# NOMIDI_Controller_001.net
KiCad netlist of a schematic drawn in EAGLE
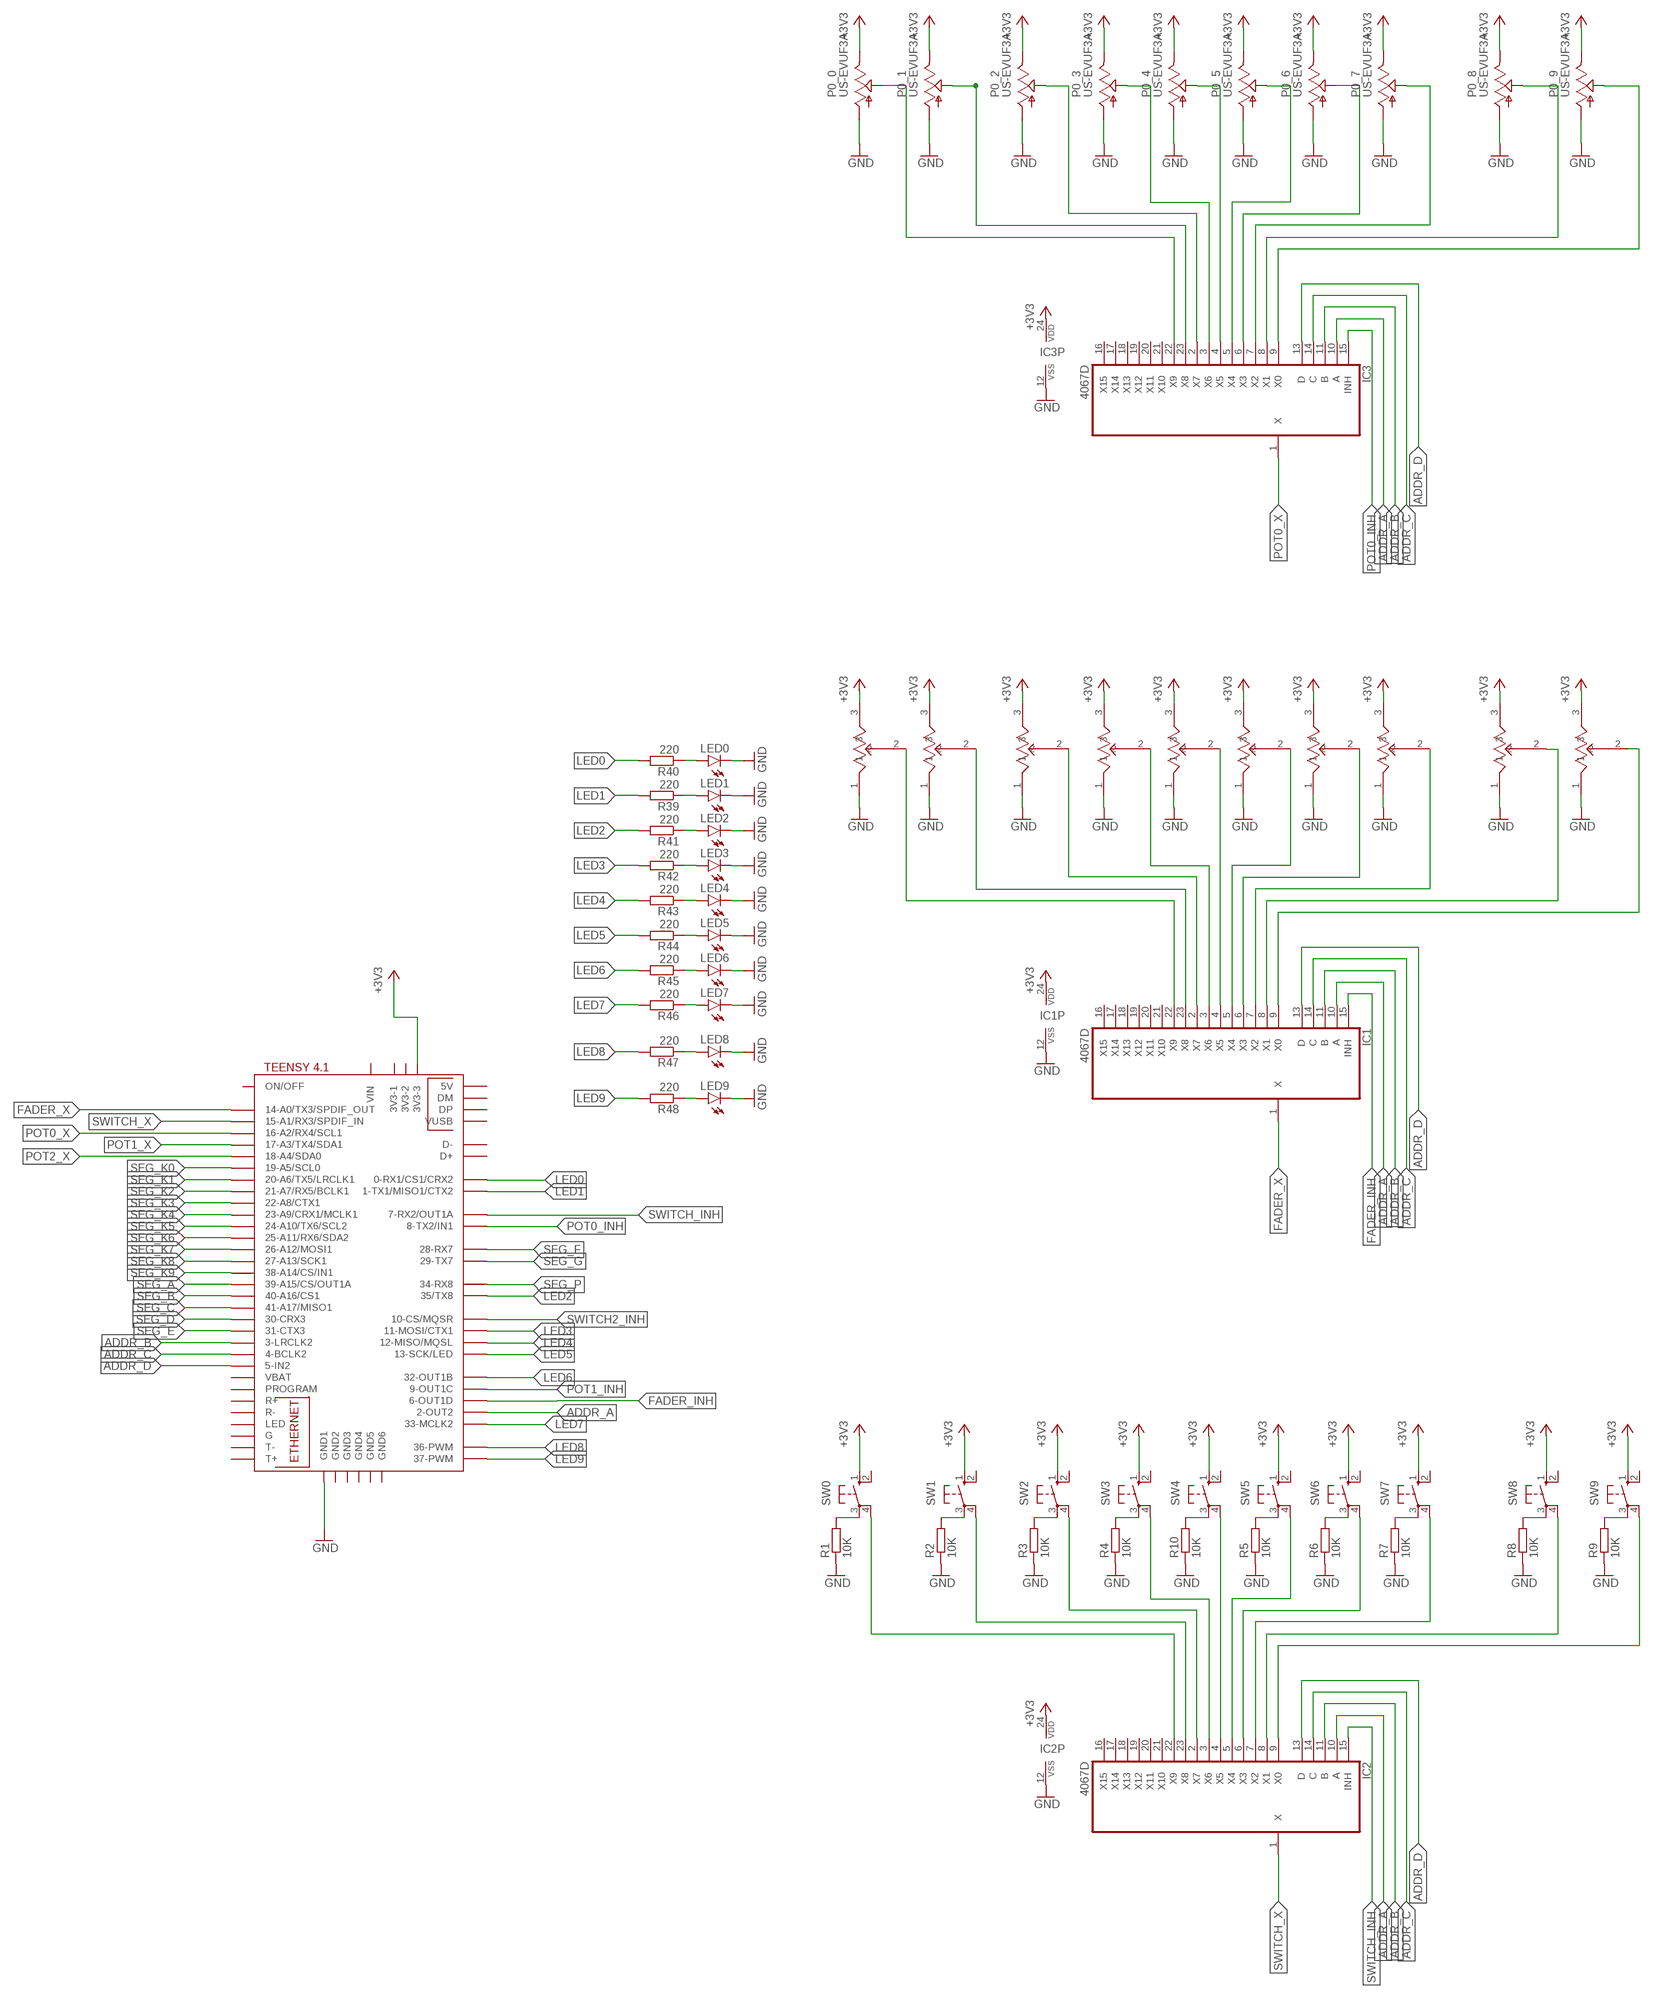
[diagram p0: schematic, sheet 1, part 1 of 3]
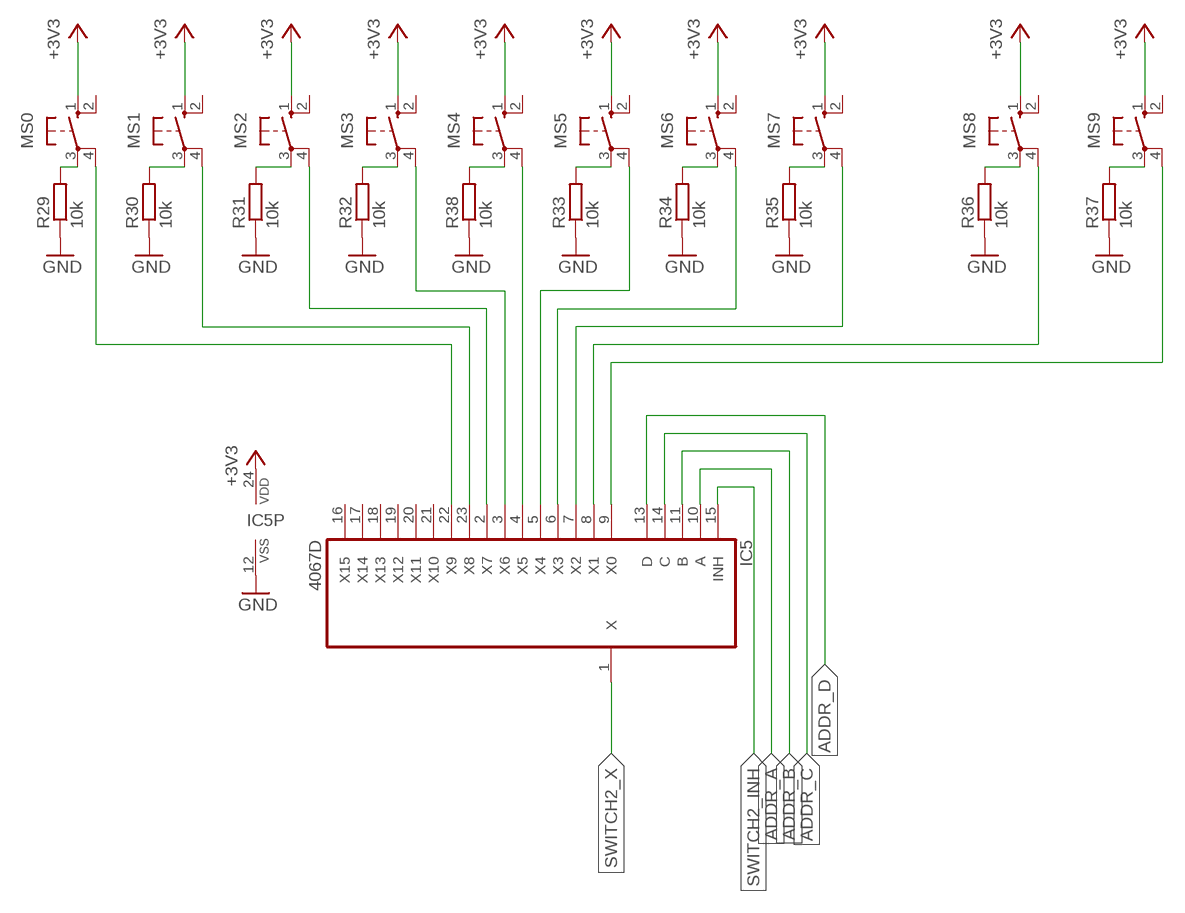
[diagram p1: schematic, sheet 1, part 2 of 3]
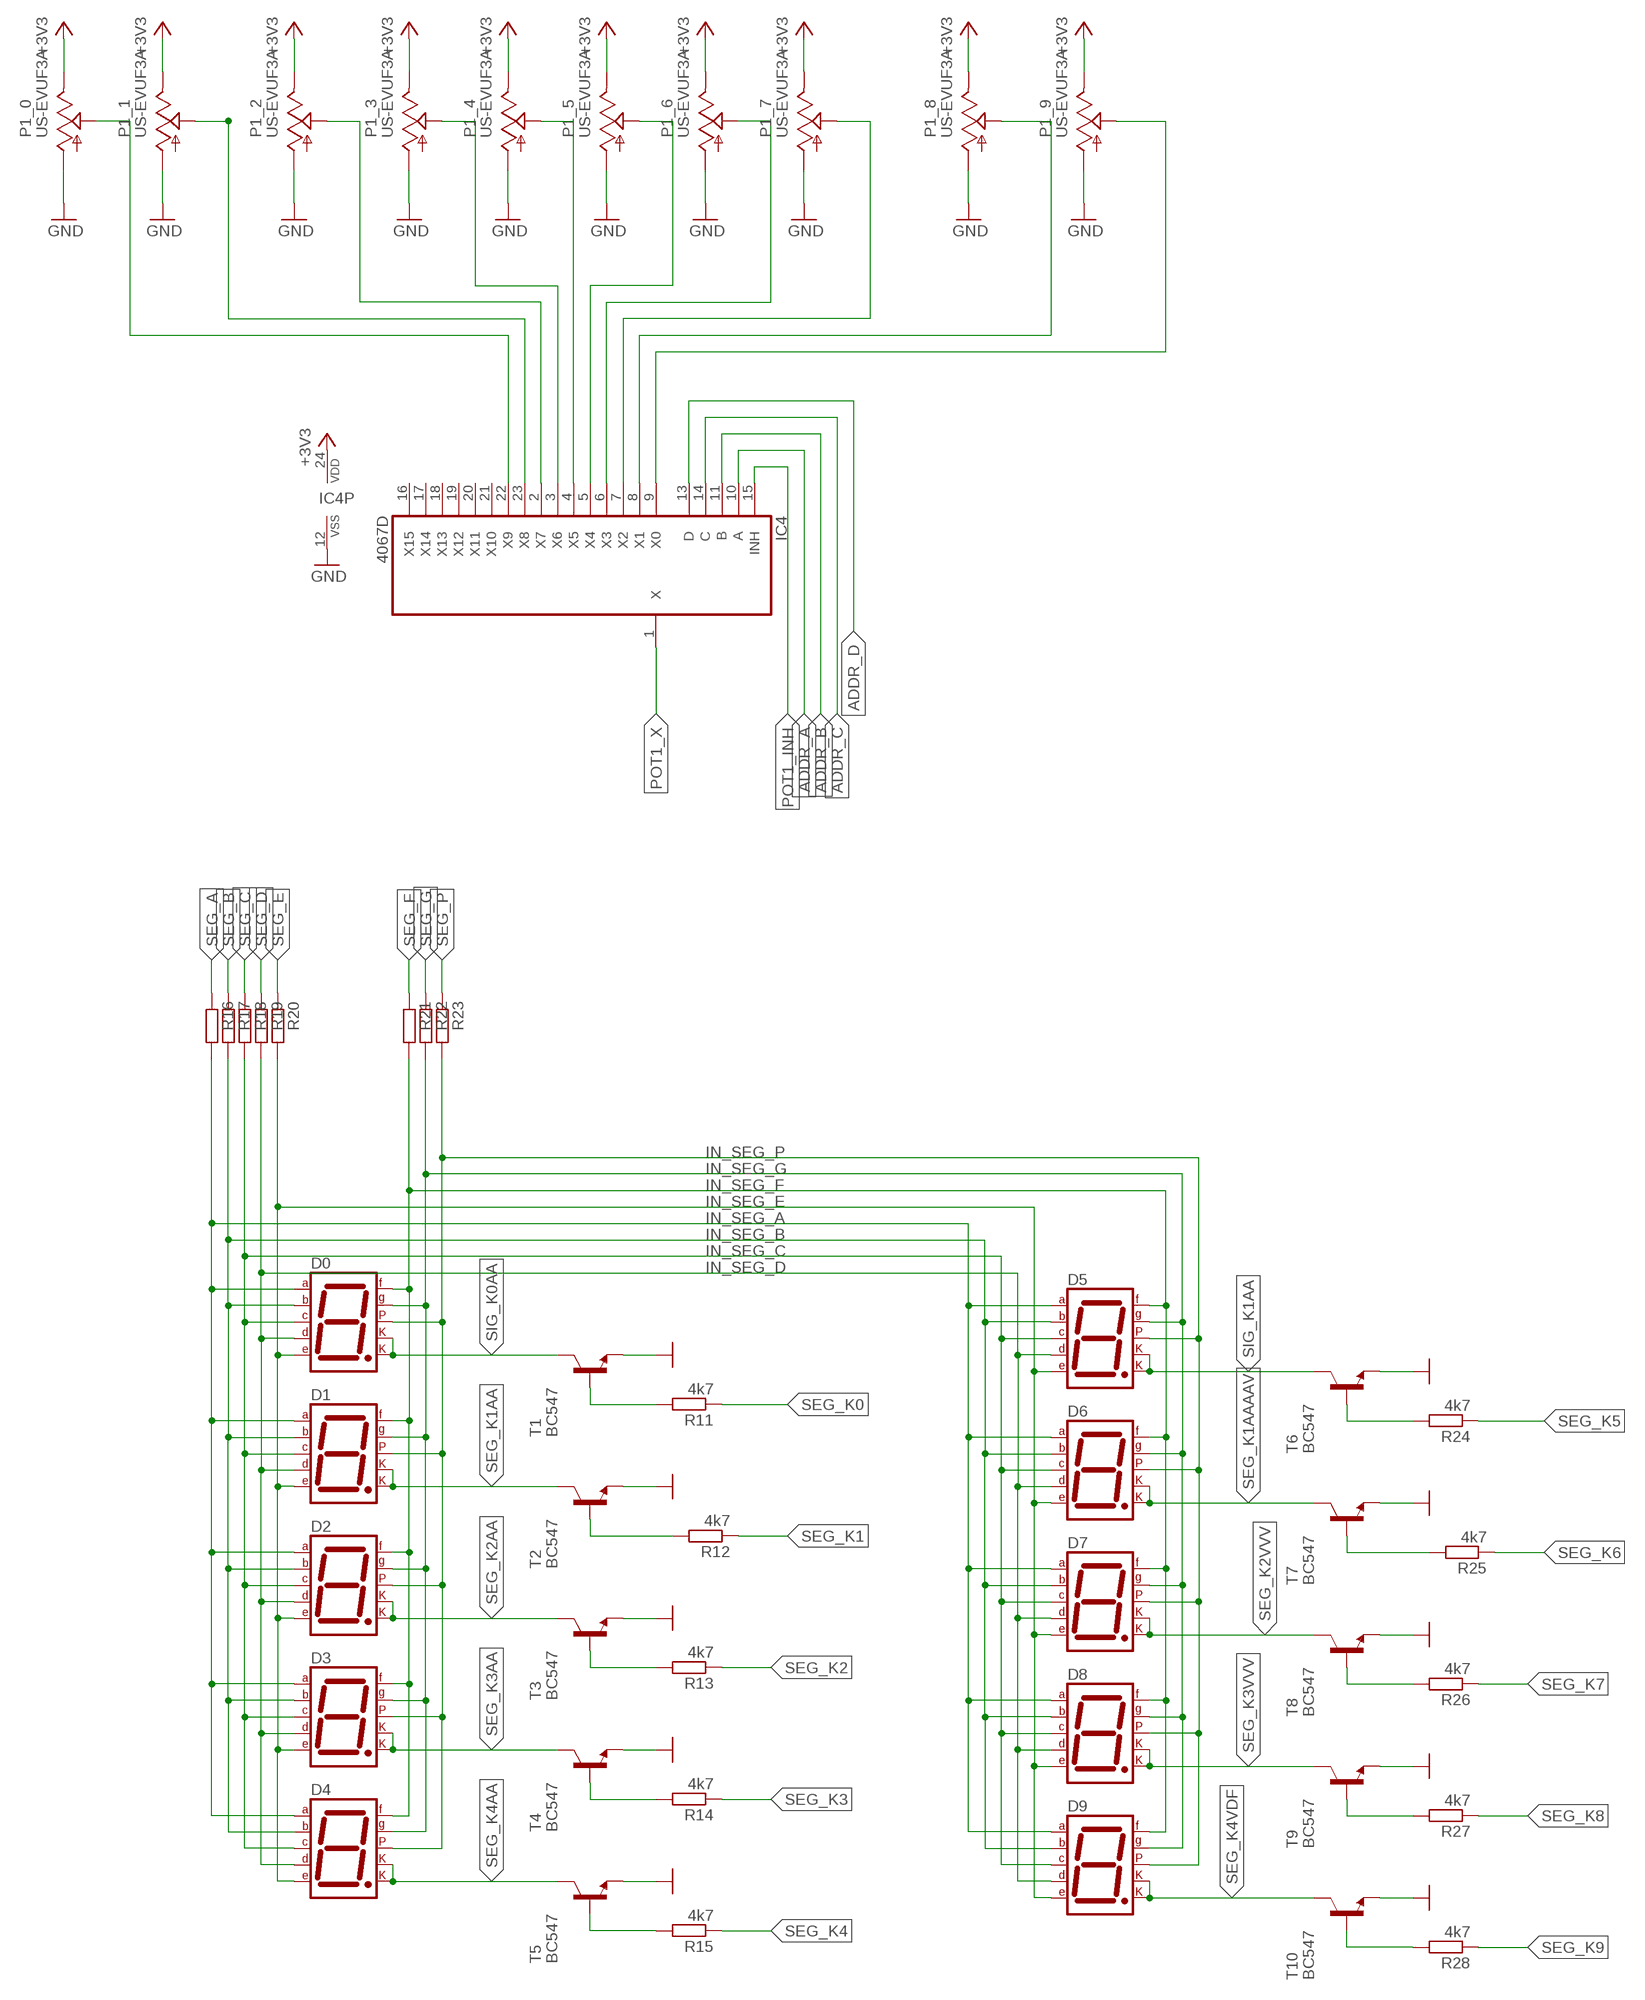
[diagram p2: schematic, sheet 1, part 3 of 3]

(export (version "E")
  (design (tool "Eeschema 10.0.6"))
  (components
    (comp (ref "D0")
      (value "7SEG-CK")
      (footprint "eagle-import:7SEG-13")
      (libsource (lib "eagle-import") (part "7SEG-CK"))
    )
    (comp (ref "D1")
      (value "7SEG-CK")
      (footprint "eagle-import:7SEG-13")
      (libsource (lib "eagle-import") (part "7SEG-CK"))
    )
    (comp (ref "D2")
      (value "7SEG-CK")
      (footprint "eagle-import:7SEG-13")
      (libsource (lib "eagle-import") (part "7SEG-CK"))
    )
    (comp (ref "D3")
      (value "7SEG-CK")
      (footprint "eagle-import:7SEG-13")
      (libsource (lib "eagle-import") (part "7SEG-CK"))
    )
    (comp (ref "D4")
      (value "7SEG-CK")
      (footprint "eagle-import:7SEG-13")
      (libsource (lib "eagle-import") (part "7SEG-CK"))
    )
    (comp (ref "D5")
      (value "7SEG-CK")
      (footprint "eagle-import:7SEG-13")
      (libsource (lib "eagle-import") (part "7SEG-CK"))
    )
    (comp (ref "D6")
      (value "7SEG-CK")
      (footprint "eagle-import:7SEG-13")
      (libsource (lib "eagle-import") (part "7SEG-CK"))
    )
    (comp (ref "D7")
      (value "7SEG-CK")
      (footprint "eagle-import:7SEG-13")
      (libsource (lib "eagle-import") (part "7SEG-CK"))
    )
    (comp (ref "D8")
      (value "7SEG-CK")
      (footprint "eagle-import:7SEG-13")
      (libsource (lib "eagle-import") (part "7SEG-CK"))
    )
    (comp (ref "D9")
      (value "7SEG-CK")
      (footprint "eagle-import:7SEG-13")
      (libsource (lib "eagle-import") (part "7SEG-CK"))
    )
    (comp (ref "IC1")
      (value "4067D")
      (footprint "eagle-import:SO24W")
      (libsource (lib "eagle-import") (part "4067D"))
    )
    (comp (ref "IC2")
      (value "4067D")
      (footprint "eagle-import:SO24W")
      (libsource (lib "eagle-import") (part "4067D"))
    )
    (comp (ref "IC3")
      (value "4067D")
      (footprint "eagle-import:SO24W")
      (libsource (lib "eagle-import") (part "4067D"))
    )
    (comp (ref "IC4")
      (value "4067D")
      (footprint "eagle-import:SO24W")
      (libsource (lib "eagle-import") (part "4067D"))
    )
    (comp (ref "IC5")
      (value "4067D")
      (footprint "eagle-import:SO24W")
      (libsource (lib "eagle-import") (part "4067D"))
    )
    (comp (ref "LED0")
      (value "LED3MM")
      (footprint "eagle-import:LED3MM")
      (libsource (lib "eagle-import") (part "LED3MM"))
    )
    (comp (ref "LED1")
      (value "LED3MM")
      (footprint "eagle-import:LED3MM")
      (libsource (lib "eagle-import") (part "LED3MM"))
    )
    (comp (ref "LED2")
      (value "LED3MM")
      (footprint "eagle-import:LED3MM")
      (libsource (lib "eagle-import") (part "LED3MM"))
    )
    (comp (ref "LED3")
      (value "LED3MM")
      (footprint "eagle-import:LED3MM")
      (libsource (lib "eagle-import") (part "LED3MM"))
    )
    (comp (ref "LED4")
      (value "LED3MM")
      (footprint "eagle-import:LED3MM")
      (libsource (lib "eagle-import") (part "LED3MM"))
    )
    (comp (ref "LED5")
      (value "LED3MM")
      (footprint "eagle-import:LED3MM")
      (libsource (lib "eagle-import") (part "LED3MM"))
    )
    (comp (ref "LED6")
      (value "LED3MM")
      (footprint "eagle-import:LED3MM")
      (libsource (lib "eagle-import") (part "LED3MM"))
    )
    (comp (ref "LED7")
      (value "LED3MM")
      (footprint "eagle-import:LED3MM")
      (libsource (lib "eagle-import") (part "LED3MM"))
    )
    (comp (ref "LED8")
      (value "LED3MM")
      (footprint "eagle-import:LED3MM")
      (libsource (lib "eagle-import") (part "LED3MM"))
    )
    (comp (ref "LED9")
      (value "LED3MM")
      (footprint "eagle-import:LED3MM")
      (libsource (lib "eagle-import") (part "LED3MM"))
    )
    (comp (ref "M0")
      (value "SLIDEPOT-ALPS-60MM")
      (footprint "eagle-import:RS6011SP600")
      (libsource (lib "eagle-import") (part "SLIDEPOT-ALPS-60MM"))
    )
    (comp (ref "M1")
      (value "SLIDEPOT-ALPS-60MM")
      (footprint "eagle-import:RS6011SP600")
      (libsource (lib "eagle-import") (part "SLIDEPOT-ALPS-60MM"))
    )
    (comp (ref "MS0")
      (value "10-XX")
      (footprint "eagle-import:B3F-10XX")
      (fields (field (name "MPN") "B3F-1000"))
      (libsource (lib "eagle-import") (part "10-XX"))
    )
    (comp (ref "MS1")
      (value "10-XX")
      (footprint "eagle-import:B3F-10XX")
      (fields (field (name "MPN") "B3F-1000"))
      (libsource (lib "eagle-import") (part "10-XX"))
    )
    (comp (ref "MS2")
      (value "10-XX")
      (footprint "eagle-import:B3F-10XX")
      (fields (field (name "MPN") "B3F-1000"))
      (libsource (lib "eagle-import") (part "10-XX"))
    )
    (comp (ref "MS3")
      (value "10-XX")
      (footprint "eagle-import:B3F-10XX")
      (fields (field (name "MPN") "B3F-1000"))
      (libsource (lib "eagle-import") (part "10-XX"))
    )
    (comp (ref "MS4")
      (value "10-XX")
      (footprint "eagle-import:B3F-10XX")
      (fields (field (name "MPN") "B3F-1000"))
      (libsource (lib "eagle-import") (part "10-XX"))
    )
    (comp (ref "MS5")
      (value "10-XX")
      (footprint "eagle-import:B3F-10XX")
      (fields (field (name "MPN") "B3F-1000"))
      (libsource (lib "eagle-import") (part "10-XX"))
    )
    (comp (ref "MS6")
      (value "10-XX")
      (footprint "eagle-import:B3F-10XX")
      (fields (field (name "MPN") "B3F-1000"))
      (libsource (lib "eagle-import") (part "10-XX"))
    )
    (comp (ref "MS7")
      (value "10-XX")
      (footprint "eagle-import:B3F-10XX")
      (fields (field (name "MPN") "B3F-1000"))
      (libsource (lib "eagle-import") (part "10-XX"))
    )
    (comp (ref "MS8")
      (value "10-XX")
      (footprint "eagle-import:B3F-10XX")
      (fields (field (name "MPN") "B3F-1000"))
      (libsource (lib "eagle-import") (part "10-XX"))
    )
    (comp (ref "MS9")
      (value "10-XX")
      (footprint "eagle-import:B3F-10XX")
      (fields (field (name "MPN") "B3F-1000"))
      (libsource (lib "eagle-import") (part "10-XX"))
    )
    (comp (ref "P0_0")
      (value "US-EVUF3A")
      (footprint "eagle-import:EVUF")
      (libsource (lib "eagle-import") (part "US-EVUAF3"))
    )
    (comp (ref "P0_1")
      (value "US-EVUF3A")
      (footprint "eagle-import:EVUF")
      (libsource (lib "eagle-import") (part "US-EVUAF3"))
    )
    (comp (ref "P0_2")
      (value "US-EVUF3A")
      (footprint "eagle-import:EVUF")
      (libsource (lib "eagle-import") (part "US-EVUAF3"))
    )
    (comp (ref "P0_3")
      (value "US-EVUF3A")
      (footprint "eagle-import:EVUF")
      (libsource (lib "eagle-import") (part "US-EVUAF3"))
    )
    (comp (ref "P0_4")
      (value "US-EVUF3A")
      (footprint "eagle-import:EVUF")
      (libsource (lib "eagle-import") (part "US-EVUAF3"))
    )
    (comp (ref "P0_5")
      (value "US-EVUF3A")
      (footprint "eagle-import:EVUF")
      (libsource (lib "eagle-import") (part "US-EVUAF3"))
    )
    (comp (ref "P0_6")
      (value "US-EVUF3A")
      (footprint "eagle-import:EVUF")
      (libsource (lib "eagle-import") (part "US-EVUAF3"))
    )
    (comp (ref "P0_7")
      (value "US-EVUF3A")
      (footprint "eagle-import:EVUF")
      (libsource (lib "eagle-import") (part "US-EVUAF3"))
    )
    (comp (ref "P0_8")
      (value "US-EVUF3A")
      (footprint "eagle-import:EVUF")
      (libsource (lib "eagle-import") (part "US-EVUAF3"))
    )
    (comp (ref "P0_9")
      (value "US-EVUF3A")
      (footprint "eagle-import:EVUF")
      (libsource (lib "eagle-import") (part "US-EVUAF3"))
    )
    (comp (ref "P1_0")
      (value "US-EVUF3A")
      (footprint "eagle-import:EVUF")
      (libsource (lib "eagle-import") (part "US-EVUAF3"))
    )
    (comp (ref "P1_1")
      (value "US-EVUF3A")
      (footprint "eagle-import:EVUF")
      (libsource (lib "eagle-import") (part "US-EVUAF3"))
    )
    (comp (ref "P1_2")
      (value "US-EVUF3A")
      (footprint "eagle-import:EVUF")
      (libsource (lib "eagle-import") (part "US-EVUAF3"))
    )
    (comp (ref "P1_3")
      (value "US-EVUF3A")
      (footprint "eagle-import:EVUF")
      (libsource (lib "eagle-import") (part "US-EVUAF3"))
    )
    (comp (ref "P1_4")
      (value "US-EVUF3A")
      (footprint "eagle-import:EVUF")
      (libsource (lib "eagle-import") (part "US-EVUAF3"))
    )
    (comp (ref "P1_5")
      (value "US-EVUF3A")
      (footprint "eagle-import:EVUF")
      (libsource (lib "eagle-import") (part "US-EVUAF3"))
    )
    (comp (ref "P1_6")
      (value "US-EVUF3A")
      (footprint "eagle-import:EVUF")
      (libsource (lib "eagle-import") (part "US-EVUAF3"))
    )
    (comp (ref "P1_7")
      (value "US-EVUF3A")
      (footprint "eagle-import:EVUF")
      (libsource (lib "eagle-import") (part "US-EVUAF3"))
    )
    (comp (ref "P1_8")
      (value "US-EVUF3A")
      (footprint "eagle-import:EVUF")
      (libsource (lib "eagle-import") (part "US-EVUAF3"))
    )
    (comp (ref "P1_9")
      (value "US-EVUF3A")
      (footprint "eagle-import:EVUF")
      (libsource (lib "eagle-import") (part "US-EVUAF3"))
    )
    (comp (ref "R1")
      (value "10K")
      (footprint "eagle-import:0207_7")
      (libsource (lib "eagle-import") (part "R-EU_0207/7"))
    )
    (comp (ref "R2")
      (value "10K")
      (footprint "eagle-import:0207_7")
      (libsource (lib "eagle-import") (part "R-EU_0207/7"))
    )
    (comp (ref "R3")
      (value "10K")
      (footprint "eagle-import:0207_7")
      (libsource (lib "eagle-import") (part "R-EU_0207/7"))
    )
    (comp (ref "R4")
      (value "10K")
      (footprint "eagle-import:0207_7")
      (libsource (lib "eagle-import") (part "R-EU_0207/7"))
    )
    (comp (ref "R5")
      (value "10K")
      (footprint "eagle-import:0207_7")
      (libsource (lib "eagle-import") (part "R-EU_0207/7"))
    )
    (comp (ref "R6")
      (value "10K")
      (footprint "eagle-import:0207_7")
      (libsource (lib "eagle-import") (part "R-EU_0207/7"))
    )
    (comp (ref "R7")
      (value "10K")
      (footprint "eagle-import:0207_7")
      (libsource (lib "eagle-import") (part "R-EU_0207/7"))
    )
    (comp (ref "R8")
      (value "10K")
      (footprint "eagle-import:0207_7")
      (libsource (lib "eagle-import") (part "R-EU_0207/7"))
    )
    (comp (ref "R9")
      (value "10K")
      (footprint "eagle-import:0207_7")
      (libsource (lib "eagle-import") (part "R-EU_0207/7"))
    )
    (comp (ref "R10")
      (value "10K")
      (footprint "eagle-import:0207_7")
      (libsource (lib "eagle-import") (part "R-EU_0207/7"))
    )
    (comp (ref "R11")
      (value "4k7")
      (footprint "eagle-import:0207_7")
      (libsource (lib "eagle-import") (part "R-EU_0207/7"))
    )
    (comp (ref "R12")
      (value "4k7")
      (footprint "eagle-import:0207_7")
      (libsource (lib "eagle-import") (part "R-EU_0207/7"))
    )
    (comp (ref "R13")
      (value "4k7")
      (footprint "eagle-import:0207_7")
      (libsource (lib "eagle-import") (part "R-EU_0207/7"))
    )
    (comp (ref "R14")
      (value "4k7")
      (footprint "eagle-import:0207_7")
      (libsource (lib "eagle-import") (part "R-EU_0207/7"))
    )
    (comp (ref "R15")
      (value "4k7")
      (footprint "eagle-import:0207_7")
      (libsource (lib "eagle-import") (part "R-EU_0207/7"))
    )
    (comp (ref "R16")
      (value "R-EU_0207/7")
      (footprint "eagle-import:0207_7")
      (libsource (lib "eagle-import") (part "R-EU_0207/7"))
    )
    (comp (ref "R17")
      (value "R-EU_0207/7")
      (footprint "eagle-import:0207_7")
      (libsource (lib "eagle-import") (part "R-EU_0207/7"))
    )
    (comp (ref "R18")
      (value "R-EU_0207/7")
      (footprint "eagle-import:0207_7")
      (libsource (lib "eagle-import") (part "R-EU_0207/7"))
    )
    (comp (ref "R19")
      (value "R-EU_0207/7")
      (footprint "eagle-import:0207_7")
      (libsource (lib "eagle-import") (part "R-EU_0207/7"))
    )
    (comp (ref "R20")
      (value "R-EU_0207/7")
      (footprint "eagle-import:0207_7")
      (libsource (lib "eagle-import") (part "R-EU_0207/7"))
    )
    (comp (ref "R21")
      (value "R-EU_0207/7")
      (footprint "eagle-import:0207_7")
      (libsource (lib "eagle-import") (part "R-EU_0207/7"))
    )
    (comp (ref "R22")
      (value "R-EU_0207/7")
      (footprint "eagle-import:0207_7")
      (libsource (lib "eagle-import") (part "R-EU_0207/7"))
    )
    (comp (ref "R23")
      (value "R-EU_0207/7")
      (footprint "eagle-import:0207_7")
      (libsource (lib "eagle-import") (part "R-EU_0207/7"))
    )
    (comp (ref "R24")
      (value "4k7")
      (footprint "eagle-import:0207_7")
      (libsource (lib "eagle-import") (part "R-EU_0207/7"))
    )
    (comp (ref "R25")
      (value "4k7")
      (footprint "eagle-import:0207_7")
      (libsource (lib "eagle-import") (part "R-EU_0207/7"))
    )
    (comp (ref "R26")
      (value "4k7")
      (footprint "eagle-import:0207_7")
      (libsource (lib "eagle-import") (part "R-EU_0207/7"))
    )
    (comp (ref "R27")
      (value "4k7")
      (footprint "eagle-import:0207_7")
      (libsource (lib "eagle-import") (part "R-EU_0207/7"))
    )
    (comp (ref "R28")
      (value "4k7")
      (footprint "eagle-import:0207_7")
      (libsource (lib "eagle-import") (part "R-EU_0207/7"))
    )
    (comp (ref "R29")
      (value "10k")
      (footprint "eagle-import:0207_7")
      (libsource (lib "eagle-import") (part "R-EU_0207/7"))
    )
    (comp (ref "R30")
      (value "10k")
      (footprint "eagle-import:0207_7")
      (libsource (lib "eagle-import") (part "R-EU_0207/7"))
    )
    (comp (ref "R31")
      (value "10k")
      (footprint "eagle-import:0207_7")
      (libsource (lib "eagle-import") (part "R-EU_0207/7"))
    )
    (comp (ref "R32")
      (value "10k")
      (footprint "eagle-import:0207_7")
      (libsource (lib "eagle-import") (part "R-EU_0207/7"))
    )
    (comp (ref "R33")
      (value "10k")
      (footprint "eagle-import:0207_7")
      (libsource (lib "eagle-import") (part "R-EU_0207/7"))
    )
    (comp (ref "R34")
      (value "10k")
      (footprint "eagle-import:0207_7")
      (libsource (lib "eagle-import") (part "R-EU_0207/7"))
    )
    (comp (ref "R35")
      (value "10k")
      (footprint "eagle-import:0207_7")
      (libsource (lib "eagle-import") (part "R-EU_0207/7"))
    )
    (comp (ref "R36")
      (value "10k")
      (footprint "eagle-import:0207_7")
      (libsource (lib "eagle-import") (part "R-EU_0207/7"))
    )
    (comp (ref "R37")
      (value "10k")
      (footprint "eagle-import:0207_7")
      (libsource (lib "eagle-import") (part "R-EU_0207/7"))
    )
    (comp (ref "R38")
      (value "10k")
      (footprint "eagle-import:0207_7")
      (libsource (lib "eagle-import") (part "R-EU_0207/7"))
    )
    (comp (ref "R39")
      (value "220")
      (footprint "eagle-import:0207_7")
      (libsource (lib "eagle-import") (part "R-EU_0207/7"))
    )
    (comp (ref "R40")
      (value "220")
      (footprint "eagle-import:0207_7")
      (libsource (lib "eagle-import") (part "R-EU_0207/7"))
    )
    (comp (ref "R41")
      (value "220")
      (footprint "eagle-import:0207_7")
      (libsource (lib "eagle-import") (part "R-EU_0207/7"))
    )
    (comp (ref "R42")
      (value "220")
      (footprint "eagle-import:0207_7")
      (libsource (lib "eagle-import") (part "R-EU_0207/7"))
    )
    (comp (ref "R43")
      (value "220")
      (footprint "eagle-import:0207_7")
      (libsource (lib "eagle-import") (part "R-EU_0207/7"))
    )
    (comp (ref "R44")
      (value "220")
      (footprint "eagle-import:0207_7")
      (libsource (lib "eagle-import") (part "R-EU_0207/7"))
    )
    (comp (ref "R45")
      (value "220")
      (footprint "eagle-import:0207_7")
      (libsource (lib "eagle-import") (part "R-EU_0207/7"))
    )
    (comp (ref "R46")
      (value "220")
      (footprint "eagle-import:0207_7")
      (libsource (lib "eagle-import") (part "R-EU_0207/7"))
    )
    (comp (ref "R47")
      (value "220")
      (footprint "eagle-import:0207_7")
      (libsource (lib "eagle-import") (part "R-EU_0207/7"))
    )
    (comp (ref "R48")
      (value "220")
      (footprint "eagle-import:0207_7")
      (libsource (lib "eagle-import") (part "R-EU_0207/7"))
    )
    (comp (ref "S0")
      (value "SLIDEPOT-ALPS-60MM")
      (footprint "eagle-import:RS6011SP600")
      (libsource (lib "eagle-import") (part "SLIDEPOT-ALPS-60MM"))
    )
    (comp (ref "S1")
      (value "SLIDEPOT-ALPS-60MM")
      (footprint "eagle-import:RS6011SP600")
      (libsource (lib "eagle-import") (part "SLIDEPOT-ALPS-60MM"))
    )
    (comp (ref "S2")
      (value "SLIDEPOT-ALPS-60MM")
      (footprint "eagle-import:RS6011SP600")
      (libsource (lib "eagle-import") (part "SLIDEPOT-ALPS-60MM"))
    )
    (comp (ref "S3")
      (value "SLIDEPOT-ALPS-60MM")
      (footprint "eagle-import:RS6011SP600")
      (libsource (lib "eagle-import") (part "SLIDEPOT-ALPS-60MM"))
    )
    (comp (ref "S4")
      (value "SLIDEPOT-ALPS-60MM")
      (footprint "eagle-import:RS6011SP600")
      (libsource (lib "eagle-import") (part "SLIDEPOT-ALPS-60MM"))
    )
    (comp (ref "S5")
      (value "SLIDEPOT-ALPS-60MM")
      (footprint "eagle-import:RS6011SP600")
      (libsource (lib "eagle-import") (part "SLIDEPOT-ALPS-60MM"))
    )
    (comp (ref "S6")
      (value "SLIDEPOT-ALPS-60MM")
      (footprint "eagle-import:RS6011SP600")
      (libsource (lib "eagle-import") (part "SLIDEPOT-ALPS-60MM"))
    )
    (comp (ref "S7")
      (value "SLIDEPOT-ALPS-60MM")
      (footprint "eagle-import:RS6011SP600")
      (libsource (lib "eagle-import") (part "SLIDEPOT-ALPS-60MM"))
    )
    (comp (ref "SW0")
      (value "10-XX")
      (footprint "eagle-import:B3F-10XX")
      (fields (field (name "MPN") "B3F-1000"))
      (libsource (lib "eagle-import") (part "10-XX"))
    )
    (comp (ref "SW1")
      (value "10-XX")
      (footprint "eagle-import:B3F-10XX")
      (fields (field (name "MPN") "B3F-1000"))
      (libsource (lib "eagle-import") (part "10-XX"))
    )
    (comp (ref "SW2")
      (value "10-XX")
      (footprint "eagle-import:B3F-10XX")
      (fields (field (name "MPN") "B3F-1000"))
      (libsource (lib "eagle-import") (part "10-XX"))
    )
    (comp (ref "SW3")
      (value "10-XX")
      (footprint "eagle-import:B3F-10XX")
      (fields (field (name "MPN") "B3F-1000"))
      (libsource (lib "eagle-import") (part "10-XX"))
    )
    (comp (ref "SW4")
      (value "10-XX")
      (footprint "eagle-import:B3F-10XX")
      (fields (field (name "MPN") "B3F-1000"))
      (libsource (lib "eagle-import") (part "10-XX"))
    )
    (comp (ref "SW5")
      (value "10-XX")
      (footprint "eagle-import:B3F-10XX")
      (fields (field (name "MPN") "B3F-1000"))
      (libsource (lib "eagle-import") (part "10-XX"))
    )
    (comp (ref "SW6")
      (value "10-XX")
      (footprint "eagle-import:B3F-10XX")
      (fields (field (name "MPN") "B3F-1000"))
      (libsource (lib "eagle-import") (part "10-XX"))
    )
    (comp (ref "SW7")
      (value "10-XX")
      (footprint "eagle-import:B3F-10XX")
      (fields (field (name "MPN") "B3F-1000"))
      (libsource (lib "eagle-import") (part "10-XX"))
    )
    (comp (ref "SW8")
      (value "10-XX")
      (footprint "eagle-import:B3F-10XX")
      (fields (field (name "MPN") "B3F-1000"))
      (libsource (lib "eagle-import") (part "10-XX"))
    )
    (comp (ref "SW9")
      (value "10-XX")
      (footprint "eagle-import:B3F-10XX")
      (fields (field (name "MPN") "B3F-1000"))
      (libsource (lib "eagle-import") (part "10-XX"))
    )
    (comp (ref "T1")
      (value "BC547")
      (footprint "eagle-import:TO92")
      (libsource (lib "eagle-import") (part "BC547"))
    )
    (comp (ref "T2")
      (value "BC547")
      (footprint "eagle-import:TO92")
      (libsource (lib "eagle-import") (part "BC547"))
    )
    (comp (ref "T3")
      (value "BC547")
      (footprint "eagle-import:TO92")
      (libsource (lib "eagle-import") (part "BC547"))
    )
    (comp (ref "T4")
      (value "BC547")
      (footprint "eagle-import:TO92")
      (libsource (lib "eagle-import") (part "BC547"))
    )
    (comp (ref "T5")
      (value "BC547")
      (footprint "eagle-import:TO92")
      (libsource (lib "eagle-import") (part "BC547"))
    )
    (comp (ref "T6")
      (value "BC547")
      (footprint "eagle-import:TO92")
      (libsource (lib "eagle-import") (part "BC547"))
    )
    (comp (ref "T7")
      (value "BC547")
      (footprint "eagle-import:TO92")
      (libsource (lib "eagle-import") (part "BC547"))
    )
    (comp (ref "T8")
      (value "BC547")
      (footprint "eagle-import:TO92")
      (libsource (lib "eagle-import") (part "BC547"))
    )
    (comp (ref "T9")
      (value "BC547")
      (footprint "eagle-import:TO92")
      (libsource (lib "eagle-import") (part "BC547"))
    )
    (comp (ref "T10")
      (value "BC547")
      (footprint "eagle-import:TO92")
      (libsource (lib "eagle-import") (part "BC547"))
    )
    (comp (ref "U$1")
      (value "TEENSY41")
      (footprint "eagle-import:TEENSY41")
      (libsource (lib "eagle-import") (part "TEENSY41"))
    )
  )
  (nets
    (net (code "1") (name "+3V3") (class "Default")
      (node (ref "IC1") (pin "24") (pinfunction "VDD_24") (pintype "power_in"))
      (node (ref "IC2") (pin "24") (pinfunction "VDD_24") (pintype "power_in"))
      (node (ref "IC3") (pin "24") (pinfunction "VDD_24") (pintype "power_in"))
      (node (ref "IC4") (pin "24") (pinfunction "VDD_24") (pintype "power_in"))
      (node (ref "IC5") (pin "24") (pinfunction "VDD_24") (pintype "power_in"))
      (node (ref "M0") (pin "3") (pinfunction "3_3") (pintype "bidirectional"))
      (node (ref "M1") (pin "3") (pinfunction "3_3") (pintype "bidirectional"))
      (node (ref "MS0") (pin "1") (pinfunction "S_1") (pintype "passive"))
      (node (ref "MS1") (pin "1") (pinfunction "S_1") (pintype "passive"))
      (node (ref "MS2") (pin "1") (pinfunction "S_1") (pintype "passive"))
      (node (ref "MS3") (pin "1") (pinfunction "S_1") (pintype "passive"))
      (node (ref "MS4") (pin "1") (pinfunction "S_1") (pintype "passive"))
      (node (ref "MS5") (pin "1") (pinfunction "S_1") (pintype "passive"))
      (node (ref "MS6") (pin "1") (pinfunction "S_1") (pintype "passive"))
      (node (ref "MS7") (pin "1") (pinfunction "S_1") (pintype "passive"))
      (node (ref "MS8") (pin "1") (pinfunction "S_1") (pintype "passive"))
      (node (ref "MS9") (pin "1") (pinfunction "S_1") (pintype "passive"))
      (node (ref "P0_0") (pin "3") (pinfunction "E_3") (pintype "passive"))
      (node (ref "P0_1") (pin "3") (pinfunction "E_3") (pintype "passive"))
      (node (ref "P0_2") (pin "3") (pinfunction "E_3") (pintype "passive"))
      (node (ref "P0_3") (pin "3") (pinfunction "E_3") (pintype "passive"))
      (node (ref "P0_4") (pin "3") (pinfunction "E_3") (pintype "passive"))
      (node (ref "P0_5") (pin "3") (pinfunction "E_3") (pintype "passive"))
      (node (ref "P0_6") (pin "3") (pinfunction "E_3") (pintype "passive"))
      (node (ref "P0_7") (pin "3") (pinfunction "E_3") (pintype "passive"))
      (node (ref "P0_8") (pin "3") (pinfunction "E_3") (pintype "passive"))
      (node (ref "P0_9") (pin "3") (pinfunction "E_3") (pintype "passive"))
      (node (ref "P1_0") (pin "3") (pinfunction "E_3") (pintype "passive"))
      (node (ref "P1_1") (pin "3") (pinfunction "E_3") (pintype "passive"))
      (node (ref "P1_2") (pin "3") (pinfunction "E_3") (pintype "passive"))
      (node (ref "P1_3") (pin "3") (pinfunction "E_3") (pintype "passive"))
      (node (ref "P1_4") (pin "3") (pinfunction "E_3") (pintype "passive"))
      (node (ref "P1_5") (pin "3") (pinfunction "E_3") (pintype "passive"))
      (node (ref "P1_6") (pin "3") (pinfunction "E_3") (pintype "passive"))
      (node (ref "P1_7") (pin "3") (pinfunction "E_3") (pintype "passive"))
      (node (ref "P1_8") (pin "3") (pinfunction "E_3") (pintype "passive"))
      (node (ref "P1_9") (pin "3") (pinfunction "E_3") (pintype "passive"))
      (node (ref "S0") (pin "3") (pinfunction "3_3") (pintype "bidirectional"))
      (node (ref "S1") (pin "3") (pinfunction "3_3") (pintype "bidirectional"))
      (node (ref "S2") (pin "3") (pinfunction "3_3") (pintype "bidirectional"))
      (node (ref "S3") (pin "3") (pinfunction "3_3") (pintype "bidirectional"))
      (node (ref "S4") (pin "3") (pinfunction "3_3") (pintype "bidirectional"))
      (node (ref "S5") (pin "3") (pinfunction "3_3") (pintype "bidirectional"))
      (node (ref "S6") (pin "3") (pinfunction "3_3") (pintype "bidirectional"))
      (node (ref "S7") (pin "3") (pinfunction "3_3") (pintype "bidirectional"))
      (node (ref "SW0") (pin "1") (pinfunction "S_1") (pintype "passive"))
      (node (ref "SW1") (pin "1") (pinfunction "S_1") (pintype "passive"))
      (node (ref "SW2") (pin "1") (pinfunction "S_1") (pintype "passive"))
      (node (ref "SW3") (pin "1") (pinfunction "S_1") (pintype "passive"))
      (node (ref "SW4") (pin "1") (pinfunction "S_1") (pintype "passive"))
      (node (ref "SW5") (pin "1") (pinfunction "S_1") (pintype "passive"))
      (node (ref "SW6") (pin "1") (pinfunction "S_1") (pintype "passive"))
      (node (ref "SW7") (pin "1") (pinfunction "S_1") (pintype "passive"))
      (node (ref "SW8") (pin "1") (pinfunction "S_1") (pintype "passive"))
      (node (ref "SW9") (pin "1") (pinfunction "S_1") (pintype "passive"))
      (node (ref "U$1") (pin "3V3-3") (pinfunction "3V3-3_3V3-3") (pintype "bidirectional"))
    )
    (net (code "2") (name "/IN_SEG_A") (class "Default")
      (node (ref "D0") (pin "7") (pinfunction "A_7") (pintype "passive"))
      (node (ref "D1") (pin "7") (pinfunction "A_7") (pintype "passive"))
      (node (ref "D2") (pin "7") (pinfunction "A_7") (pintype "passive"))
      (node (ref "D3") (pin "7") (pinfunction "A_7") (pintype "passive"))
      (node (ref "D4") (pin "7") (pinfunction "A_7") (pintype "passive"))
      (node (ref "D5") (pin "7") (pinfunction "A_7") (pintype "passive"))
      (node (ref "D6") (pin "7") (pinfunction "A_7") (pintype "passive"))
      (node (ref "D7") (pin "7") (pinfunction "A_7") (pintype "passive"))
      (node (ref "D8") (pin "7") (pinfunction "A_7") (pintype "passive"))
      (node (ref "D9") (pin "7") (pinfunction "A_7") (pintype "passive"))
      (node (ref "R16") (pin "2") (pinfunction "2_2") (pintype "passive"))
    )
    (net (code "3") (name "/IN_SEG_B") (class "Default")
      (node (ref "D0") (pin "6") (pinfunction "B_6") (pintype "passive"))
      (node (ref "D1") (pin "6") (pinfunction "B_6") (pintype "passive"))
      (node (ref "D2") (pin "6") (pinfunction "B_6") (pintype "passive"))
      (node (ref "D3") (pin "6") (pinfunction "B_6") (pintype "passive"))
      (node (ref "D4") (pin "6") (pinfunction "B_6") (pintype "passive"))
      (node (ref "D5") (pin "6") (pinfunction "B_6") (pintype "passive"))
      (node (ref "D6") (pin "6") (pinfunction "B_6") (pintype "passive"))
      (node (ref "D7") (pin "6") (pinfunction "B_6") (pintype "passive"))
      (node (ref "D8") (pin "6") (pinfunction "B_6") (pintype "passive"))
      (node (ref "D9") (pin "6") (pinfunction "B_6") (pintype "passive"))
      (node (ref "R17") (pin "2") (pinfunction "2_2") (pintype "passive"))
    )
    (net (code "4") (name "/IN_SEG_C") (class "Default")
      (node (ref "D0") (pin "4") (pinfunction "C_4") (pintype "passive"))
      (node (ref "D1") (pin "4") (pinfunction "C_4") (pintype "passive"))
      (node (ref "D2") (pin "4") (pinfunction "C_4") (pintype "passive"))
      (node (ref "D3") (pin "4") (pinfunction "C_4") (pintype "passive"))
      (node (ref "D4") (pin "4") (pinfunction "C_4") (pintype "passive"))
      (node (ref "D5") (pin "4") (pinfunction "C_4") (pintype "passive"))
      (node (ref "D6") (pin "4") (pinfunction "C_4") (pintype "passive"))
      (node (ref "D7") (pin "4") (pinfunction "C_4") (pintype "passive"))
      (node (ref "D8") (pin "4") (pinfunction "C_4") (pintype "passive"))
      (node (ref "D9") (pin "4") (pinfunction "C_4") (pintype "passive"))
      (node (ref "R18") (pin "2") (pinfunction "2_2") (pintype "passive"))
    )
    (net (code "5") (name "/IN_SEG_D") (class "Default")
      (node (ref "D0") (pin "2") (pinfunction "D_2") (pintype "passive"))
      (node (ref "D1") (pin "2") (pinfunction "D_2") (pintype "passive"))
      (node (ref "D2") (pin "2") (pinfunction "D_2") (pintype "passive"))
      (node (ref "D3") (pin "2") (pinfunction "D_2") (pintype "passive"))
      (node (ref "D4") (pin "2") (pinfunction "D_2") (pintype "passive"))
      (node (ref "D5") (pin "2") (pinfunction "D_2") (pintype "passive"))
      (node (ref "D6") (pin "2") (pinfunction "D_2") (pintype "passive"))
      (node (ref "D7") (pin "2") (pinfunction "D_2") (pintype "passive"))
      (node (ref "D8") (pin "2") (pinfunction "D_2") (pintype "passive"))
      (node (ref "D9") (pin "2") (pinfunction "D_2") (pintype "passive"))
      (node (ref "R19") (pin "2") (pinfunction "2_2") (pintype "passive"))
    )
    (net (code "6") (name "/IN_SEG_E") (class "Default")
      (node (ref "D0") (pin "1") (pinfunction "E_1") (pintype "passive"))
      (node (ref "D1") (pin "1") (pinfunction "E_1") (pintype "passive"))
      (node (ref "D2") (pin "1") (pinfunction "E_1") (pintype "passive"))
      (node (ref "D3") (pin "1") (pinfunction "E_1") (pintype "passive"))
      (node (ref "D4") (pin "1") (pinfunction "E_1") (pintype "passive"))
      (node (ref "D5") (pin "1") (pinfunction "E_1") (pintype "passive"))
      (node (ref "D6") (pin "1") (pinfunction "E_1") (pintype "passive"))
      (node (ref "D7") (pin "1") (pinfunction "E_1") (pintype "passive"))
      (node (ref "D8") (pin "1") (pinfunction "E_1") (pintype "passive"))
      (node (ref "D9") (pin "1") (pinfunction "E_1") (pintype "passive"))
      (node (ref "R20") (pin "2") (pinfunction "2_2") (pintype "passive"))
    )
    (net (code "7") (name "/IN_SEG_F") (class "Default")
      (node (ref "D0") (pin "9") (pinfunction "F_9") (pintype "passive"))
      (node (ref "D1") (pin "9") (pinfunction "F_9") (pintype "passive"))
      (node (ref "D2") (pin "9") (pinfunction "F_9") (pintype "passive"))
      (node (ref "D3") (pin "9") (pinfunction "F_9") (pintype "passive"))
      (node (ref "D4") (pin "9") (pinfunction "F_9") (pintype "passive"))
      (node (ref "D5") (pin "9") (pinfunction "F_9") (pintype "passive"))
      (node (ref "D6") (pin "9") (pinfunction "F_9") (pintype "passive"))
      (node (ref "D7") (pin "9") (pinfunction "F_9") (pintype "passive"))
      (node (ref "D8") (pin "9") (pinfunction "F_9") (pintype "passive"))
      (node (ref "D9") (pin "9") (pinfunction "F_9") (pintype "passive"))
      (node (ref "R21") (pin "2") (pinfunction "2_2") (pintype "passive"))
    )
    (net (code "8") (name "/IN_SEG_G") (class "Default")
      (node (ref "D0") (pin "10") (pinfunction "G_10") (pintype "passive"))
      (node (ref "D1") (pin "10") (pinfunction "G_10") (pintype "passive"))
      (node (ref "D2") (pin "10") (pinfunction "G_10") (pintype "passive"))
      (node (ref "D3") (pin "10") (pinfunction "G_10") (pintype "passive"))
      (node (ref "D4") (pin "10") (pinfunction "G_10") (pintype "passive"))
      (node (ref "D5") (pin "10") (pinfunction "G_10") (pintype "passive"))
      (node (ref "D6") (pin "10") (pinfunction "G_10") (pintype "passive"))
      (node (ref "D7") (pin "10") (pinfunction "G_10") (pintype "passive"))
      (node (ref "D8") (pin "10") (pinfunction "G_10") (pintype "passive"))
      (node (ref "D9") (pin "10") (pinfunction "G_10") (pintype "passive"))
      (node (ref "R22") (pin "2") (pinfunction "2_2") (pintype "passive"))
    )
    (net (code "9") (name "/IN_SEG_P") (class "Default")
      (node (ref "D0") (pin "5") (pinfunction "DP_5") (pintype "passive"))
      (node (ref "D1") (pin "5") (pinfunction "DP_5") (pintype "passive"))
      (node (ref "D2") (pin "5") (pinfunction "DP_5") (pintype "passive"))
      (node (ref "D3") (pin "5") (pinfunction "DP_5") (pintype "passive"))
      (node (ref "D4") (pin "5") (pinfunction "DP_5") (pintype "passive"))
      (node (ref "D5") (pin "5") (pinfunction "DP_5") (pintype "passive"))
      (node (ref "D6") (pin "5") (pinfunction "DP_5") (pintype "passive"))
      (node (ref "D7") (pin "5") (pinfunction "DP_5") (pintype "passive"))
      (node (ref "D8") (pin "5") (pinfunction "DP_5") (pintype "passive"))
      (node (ref "D9") (pin "5") (pinfunction "DP_5") (pintype "passive"))
      (node (ref "R23") (pin "2") (pinfunction "2_2") (pintype "passive"))
    )
    (net (code "10") (name "ADDR_A") (class "Default")
      (node (ref "IC1") (pin "10") (pinfunction "A_10") (pintype "input"))
      (node (ref "IC2") (pin "10") (pinfunction "A_10") (pintype "input"))
      (node (ref "IC3") (pin "10") (pinfunction "A_10") (pintype "input"))
      (node (ref "IC4") (pin "10") (pinfunction "A_10") (pintype "input"))
      (node (ref "IC5") (pin "10") (pinfunction "A_10") (pintype "input"))
      (node (ref "U$1") (pin "2-OUT2") (pinfunction "2-OUT2_2-OUT2") (pintype "bidirectional"))
    )
    (net (code "11") (name "ADDR_B") (class "Default")
      (node (ref "IC1") (pin "11") (pinfunction "B_11") (pintype "input"))
      (node (ref "IC2") (pin "11") (pinfunction "B_11") (pintype "input"))
      (node (ref "IC3") (pin "11") (pinfunction "B_11") (pintype "input"))
      (node (ref "IC4") (pin "11") (pinfunction "B_11") (pintype "input"))
      (node (ref "IC5") (pin "11") (pinfunction "B_11") (pintype "input"))
      (node (ref "U$1") (pin "3-LRCLK2") (pinfunction "3-LRCLK2_3-LRCLK2") (pintype "bidirectional"))
    )
    (net (code "12") (name "ADDR_C") (class "Default")
      (node (ref "IC1") (pin "14") (pinfunction "C_14") (pintype "input"))
      (node (ref "IC2") (pin "14") (pinfunction "C_14") (pintype "input"))
      (node (ref "IC3") (pin "14") (pinfunction "C_14") (pintype "input"))
      (node (ref "IC4") (pin "14") (pinfunction "C_14") (pintype "input"))
      (node (ref "IC5") (pin "14") (pinfunction "C_14") (pintype "input"))
      (node (ref "U$1") (pin "4-BCLK2") (pinfunction "4-BCLK2_4-BCLK2") (pintype "bidirectional"))
    )
    (net (code "13") (name "ADDR_D") (class "Default")
      (node (ref "IC1") (pin "13") (pinfunction "D_13") (pintype "input"))
      (node (ref "IC2") (pin "13") (pinfunction "D_13") (pintype "input"))
      (node (ref "IC3") (pin "13") (pinfunction "D_13") (pintype "input"))
      (node (ref "IC4") (pin "13") (pinfunction "D_13") (pintype "input"))
      (node (ref "IC5") (pin "13") (pinfunction "D_13") (pintype "input"))
      (node (ref "U$1") (pin "5-IN2") (pinfunction "5-IN2_5-IN2") (pintype "bidirectional"))
    )
    (net (code "14") (name "FADER_INH") (class "Default")
      (node (ref "IC1") (pin "15") (pinfunction "INH_15") (pintype "input"))
      (node (ref "U$1") (pin "6-OUT1D") (pinfunction "6-OUT1D_6-OUT1D") (pintype "bidirectional"))
    )
    (net (code "15") (name "FADER_X") (class "Default")
      (node (ref "IC1") (pin "1") (pinfunction "X_1") (pintype "output"))
      (node (ref "U$1") (pin "14-A0/TX3/SPDIF_OUT") (pinfunction "14-A0/TX3/SPDIF_OUT_14-A0/TX3/SPDIF_OUT") (pintype "bidirectional"))
    )
    (net (code "16") (name "GND") (class "Default")
      (node (ref "IC1") (pin "12") (pinfunction "VSS_12") (pintype "power_in"))
      (node (ref "IC2") (pin "12") (pinfunction "VSS_12") (pintype "power_in"))
      (node (ref "IC3") (pin "12") (pinfunction "VSS_12") (pintype "power_in"))
      (node (ref "IC4") (pin "12") (pinfunction "VSS_12") (pintype "power_in"))
      (node (ref "IC5") (pin "12") (pinfunction "VSS_12") (pintype "power_in"))
      (node (ref "LED0") (pin "K") (pinfunction "C_K") (pintype "passive"))
      (node (ref "LED1") (pin "K") (pinfunction "C_K") (pintype "passive"))
      (node (ref "LED2") (pin "K") (pinfunction "C_K") (pintype "passive"))
      (node (ref "LED3") (pin "K") (pinfunction "C_K") (pintype "passive"))
      (node (ref "LED4") (pin "K") (pinfunction "C_K") (pintype "passive"))
      (node (ref "LED5") (pin "K") (pinfunction "C_K") (pintype "passive"))
      (node (ref "LED6") (pin "K") (pinfunction "C_K") (pintype "passive"))
      (node (ref "LED7") (pin "K") (pinfunction "C_K") (pintype "passive"))
      (node (ref "LED8") (pin "K") (pinfunction "C_K") (pintype "passive"))
      (node (ref "LED9") (pin "K") (pinfunction "C_K") (pintype "passive"))
      (node (ref "M0") (pin "1") (pinfunction "1_1") (pintype "bidirectional"))
      (node (ref "M1") (pin "1") (pinfunction "1_1") (pintype "bidirectional"))
      (node (ref "P0_0") (pin "1") (pinfunction "A_1") (pintype "passive"))
      (node (ref "P0_1") (pin "1") (pinfunction "A_1") (pintype "passive"))
      (node (ref "P0_2") (pin "1") (pinfunction "A_1") (pintype "passive"))
      (node (ref "P0_3") (pin "1") (pinfunction "A_1") (pintype "passive"))
      (node (ref "P0_4") (pin "1") (pinfunction "A_1") (pintype "passive"))
      (node (ref "P0_5") (pin "1") (pinfunction "A_1") (pintype "passive"))
      (node (ref "P0_6") (pin "1") (pinfunction "A_1") (pintype "passive"))
      (node (ref "P0_7") (pin "1") (pinfunction "A_1") (pintype "passive"))
      (node (ref "P0_8") (pin "1") (pinfunction "A_1") (pintype "passive"))
      (node (ref "P0_9") (pin "1") (pinfunction "A_1") (pintype "passive"))
      (node (ref "P1_0") (pin "1") (pinfunction "A_1") (pintype "passive"))
      (node (ref "P1_1") (pin "1") (pinfunction "A_1") (pintype "passive"))
      (node (ref "P1_2") (pin "1") (pinfunction "A_1") (pintype "passive"))
      (node (ref "P1_3") (pin "1") (pinfunction "A_1") (pintype "passive"))
      (node (ref "P1_4") (pin "1") (pinfunction "A_1") (pintype "passive"))
      (node (ref "P1_5") (pin "1") (pinfunction "A_1") (pintype "passive"))
      (node (ref "P1_6") (pin "1") (pinfunction "A_1") (pintype "passive"))
      (node (ref "P1_7") (pin "1") (pinfunction "A_1") (pintype "passive"))
      (node (ref "P1_8") (pin "1") (pinfunction "A_1") (pintype "passive"))
      (node (ref "P1_9") (pin "1") (pinfunction "A_1") (pintype "passive"))
      (node (ref "R1") (pin "1") (pinfunction "1_1") (pintype "passive"))
      (node (ref "R10") (pin "1") (pinfunction "1_1") (pintype "passive"))
      (node (ref "R2") (pin "1") (pinfunction "1_1") (pintype "passive"))
      (node (ref "R29") (pin "1") (pinfunction "1_1") (pintype "passive"))
      (node (ref "R3") (pin "1") (pinfunction "1_1") (pintype "passive"))
      (node (ref "R30") (pin "1") (pinfunction "1_1") (pintype "passive"))
      (node (ref "R31") (pin "1") (pinfunction "1_1") (pintype "passive"))
      (node (ref "R32") (pin "1") (pinfunction "1_1") (pintype "passive"))
      (node (ref "R33") (pin "1") (pinfunction "1_1") (pintype "passive"))
      (node (ref "R34") (pin "1") (pinfunction "1_1") (pintype "passive"))
      (node (ref "R35") (pin "1") (pinfunction "1_1") (pintype "passive"))
      (node (ref "R36") (pin "1") (pinfunction "1_1") (pintype "passive"))
      (node (ref "R37") (pin "1") (pinfunction "1_1") (pintype "passive"))
      (node (ref "R38") (pin "1") (pinfunction "1_1") (pintype "passive"))
      (node (ref "R4") (pin "1") (pinfunction "1_1") (pintype "passive"))
      (node (ref "R5") (pin "1") (pinfunction "1_1") (pintype "passive"))
      (node (ref "R6") (pin "1") (pinfunction "1_1") (pintype "passive"))
      (node (ref "R7") (pin "1") (pinfunction "1_1") (pintype "passive"))
      (node (ref "R8") (pin "1") (pinfunction "1_1") (pintype "passive"))
      (node (ref "R9") (pin "1") (pinfunction "1_1") (pintype "passive"))
      (node (ref "S0") (pin "1") (pinfunction "1_1") (pintype "bidirectional"))
      (node (ref "S1") (pin "1") (pinfunction "1_1") (pintype "bidirectional"))
      (node (ref "S2") (pin "1") (pinfunction "1_1") (pintype "bidirectional"))
      (node (ref "S3") (pin "1") (pinfunction "1_1") (pintype "bidirectional"))
      (node (ref "S4") (pin "1") (pinfunction "1_1") (pintype "bidirectional"))
      (node (ref "S5") (pin "1") (pinfunction "1_1") (pintype "bidirectional"))
      (node (ref "S6") (pin "1") (pinfunction "1_1") (pintype "bidirectional"))
      (node (ref "S7") (pin "1") (pinfunction "1_1") (pintype "bidirectional"))
      (node (ref "T1") (pin "1") (pinfunction "E_1") (pintype "passive"))
      (node (ref "T10") (pin "1") (pinfunction "E_1") (pintype "passive"))
      (node (ref "T2") (pin "1") (pinfunction "E_1") (pintype "passive"))
      (node (ref "T3") (pin "1") (pinfunction "E_1") (pintype "passive"))
      (node (ref "T4") (pin "1") (pinfunction "E_1") (pintype "passive"))
      (node (ref "T5") (pin "1") (pinfunction "E_1") (pintype "passive"))
      (node (ref "T6") (pin "1") (pinfunction "E_1") (pintype "passive"))
      (node (ref "T7") (pin "1") (pinfunction "E_1") (pintype "passive"))
      (node (ref "T8") (pin "1") (pinfunction "E_1") (pintype "passive"))
      (node (ref "T9") (pin "1") (pinfunction "E_1") (pintype "passive"))
      (node (ref "U$1") (pin "GND1") (pinfunction "GND1_GND1") (pintype "bidirectional"))
    )
    (net (code "17") (name "LED0") (class "Default")
      (node (ref "R40") (pin "2") (pinfunction "2_2") (pintype "passive"))
      (node (ref "U$1") (pin "0-RX1/CS1/CRX2") (pinfunction "0-RX1/CS1/CRX2_0-RX1/CS1/CRX2") (pintype "bidirectional"))
    )
    (net (code "18") (name "LED1") (class "Default")
      (node (ref "R39") (pin "2") (pinfunction "2_2") (pintype "passive"))
      (node (ref "U$1") (pin "1-TX1/MISO1/CTX2") (pinfunction "1-TX1/MISO1/CTX2_1-TX1/MISO1/CTX2") (pintype "bidirectional"))
    )
    (net (code "19") (name "LED2") (class "Default")
      (node (ref "R41") (pin "2") (pinfunction "2_2") (pintype "passive"))
      (node (ref "U$1") (pin "35-TX8") (pinfunction "35/TX8_35-TX8") (pintype "bidirectional"))
    )
    (net (code "20") (name "LED3") (class "Default")
      (node (ref "R42") (pin "2") (pinfunction "2_2") (pintype "passive"))
      (node (ref "U$1") (pin "11-MOSI/CTX1") (pinfunction "11-MOSI/CTX1_11-MOSI/CTX1") (pintype "bidirectional"))
    )
    (net (code "21") (name "LED4") (class "Default")
      (node (ref "R43") (pin "2") (pinfunction "2_2") (pintype "passive"))
      (node (ref "U$1") (pin "12-MISO/MQSL") (pinfunction "12-MISO/MQSL_12-MISO/MQSL") (pintype "bidirectional"))
    )
    (net (code "22") (name "LED5") (class "Default")
      (node (ref "R44") (pin "2") (pinfunction "2_2") (pintype "passive"))
      (node (ref "U$1") (pin "13-SCK/LED") (pinfunction "13-SCK/LED_13-SCK/LED") (pintype "bidirectional"))
    )
    (net (code "23") (name "LED6") (class "Default")
      (node (ref "R45") (pin "2") (pinfunction "2_2") (pintype "passive"))
      (node (ref "U$1") (pin "32-OUT1B") (pinfunction "32-OUT1B_32-OUT1B") (pintype "bidirectional"))
    )
    (net (code "24") (name "LED7") (class "Default")
      (node (ref "R46") (pin "2") (pinfunction "2_2") (pintype "passive"))
      (node (ref "U$1") (pin "33-MCLK2") (pinfunction "33-MCLK2_33-MCLK2") (pintype "bidirectional"))
    )
    (net (code "25") (name "LED8") (class "Default")
      (node (ref "R47") (pin "2") (pinfunction "2_2") (pintype "passive"))
      (node (ref "U$1") (pin "36-PWM") (pinfunction "36-PWM_36-PWM") (pintype "bidirectional"))
    )
    (net (code "26") (name "LED9") (class "Default")
      (node (ref "R48") (pin "2") (pinfunction "2_2") (pintype "passive"))
      (node (ref "U$1") (pin "37-PWM") (pinfunction "37-PWM_37-PWM") (pintype "bidirectional"))
    )
    (net (code "27") (name "Net-(IC1A-X0)") (class "Default")
      (node (ref "IC1") (pin "9") (pinfunction "X0_9") (pintype "input"))
      (node (ref "M1") (pin "2") (pinfunction "2_2") (pintype "bidirectional"))
    )
    (net (code "28") (name "Net-(IC1A-X1)") (class "Default")
      (node (ref "IC1") (pin "8") (pinfunction "X1_8") (pintype "input"))
      (node (ref "M0") (pin "2") (pinfunction "2_2") (pintype "bidirectional"))
    )
    (net (code "29") (name "Net-(IC1A-X2)") (class "Default")
      (node (ref "IC1") (pin "7") (pinfunction "X2_7") (pintype "input"))
      (node (ref "S7") (pin "2") (pinfunction "2_2") (pintype "bidirectional"))
    )
    (net (code "30") (name "Net-(IC1A-X3)") (class "Default")
      (node (ref "IC1") (pin "6") (pinfunction "X3_6") (pintype "input"))
      (node (ref "S6") (pin "2") (pinfunction "2_2") (pintype "bidirectional"))
    )
    (net (code "31") (name "Net-(IC1A-X4)") (class "Default")
      (node (ref "IC1") (pin "5") (pinfunction "X4_5") (pintype "input"))
      (node (ref "S5") (pin "2") (pinfunction "2_2") (pintype "bidirectional"))
    )
    (net (code "32") (name "Net-(IC1A-X5)") (class "Default")
      (node (ref "IC1") (pin "4") (pinfunction "X5_4") (pintype "input"))
      (node (ref "S4") (pin "2") (pinfunction "2_2") (pintype "bidirectional"))
    )
    (net (code "33") (name "Net-(IC1A-X6)") (class "Default")
      (node (ref "IC1") (pin "3") (pinfunction "X6_3") (pintype "input"))
      (node (ref "S3") (pin "2") (pinfunction "2_2") (pintype "bidirectional"))
    )
    (net (code "34") (name "Net-(IC1A-X7)") (class "Default")
      (node (ref "IC1") (pin "2") (pinfunction "X7_2") (pintype "input"))
      (node (ref "S2") (pin "2") (pinfunction "2_2") (pintype "bidirectional"))
    )
    (net (code "35") (name "Net-(IC1A-X8)") (class "Default")
      (node (ref "IC1") (pin "23") (pinfunction "X8_23") (pintype "input"))
      (node (ref "S1") (pin "2") (pinfunction "2_2") (pintype "bidirectional"))
    )
    (net (code "36") (name "Net-(IC1A-X9)") (class "Default")
      (node (ref "IC1") (pin "22") (pinfunction "X9_22") (pintype "input"))
      (node (ref "S0") (pin "2") (pinfunction "2_2") (pintype "bidirectional"))
    )
    (net (code "37") (name "Net-(IC2A-X0)") (class "Default")
      (node (ref "IC2") (pin "9") (pinfunction "X0_9") (pintype "input"))
      (node (ref "SW9") (pin "4") (pinfunction "P1_4") (pintype "passive"))
    )
    (net (code "38") (name "Net-(IC2A-X1)") (class "Default")
      (node (ref "IC2") (pin "8") (pinfunction "X1_8") (pintype "input"))
      (node (ref "SW8") (pin "4") (pinfunction "P1_4") (pintype "passive"))
    )
    (net (code "39") (name "Net-(IC2A-X2)") (class "Default")
      (node (ref "IC2") (pin "7") (pinfunction "X2_7") (pintype "input"))
      (node (ref "SW7") (pin "4") (pinfunction "P1_4") (pintype "passive"))
    )
    (net (code "40") (name "Net-(IC2A-X3)") (class "Default")
      (node (ref "IC2") (pin "6") (pinfunction "X3_6") (pintype "input"))
      (node (ref "SW6") (pin "4") (pinfunction "P1_4") (pintype "passive"))
    )
    (net (code "41") (name "Net-(IC2A-X4)") (class "Default")
      (node (ref "IC2") (pin "5") (pinfunction "X4_5") (pintype "input"))
      (node (ref "SW5") (pin "4") (pinfunction "P1_4") (pintype "passive"))
    )
    (net (code "42") (name "Net-(IC2A-X5)") (class "Default")
      (node (ref "IC2") (pin "4") (pinfunction "X5_4") (pintype "input"))
      (node (ref "SW4") (pin "4") (pinfunction "P1_4") (pintype "passive"))
    )
    (net (code "43") (name "Net-(IC2A-X6)") (class "Default")
      (node (ref "IC2") (pin "3") (pinfunction "X6_3") (pintype "input"))
      (node (ref "SW3") (pin "4") (pinfunction "P1_4") (pintype "passive"))
    )
    (net (code "44") (name "Net-(IC2A-X7)") (class "Default")
      (node (ref "IC2") (pin "2") (pinfunction "X7_2") (pintype "input"))
      (node (ref "SW2") (pin "4") (pinfunction "P1_4") (pintype "passive"))
    )
    (net (code "45") (name "Net-(IC2A-X8)") (class "Default")
      (node (ref "IC2") (pin "23") (pinfunction "X8_23") (pintype "input"))
      (node (ref "SW1") (pin "4") (pinfunction "P1_4") (pintype "passive"))
    )
    (net (code "46") (name "Net-(IC2A-X9)") (class "Default")
      (node (ref "IC2") (pin "22") (pinfunction "X9_22") (pintype "input"))
      (node (ref "SW0") (pin "4") (pinfunction "P1_4") (pintype "passive"))
    )
    (net (code "47") (name "Net-(IC3A-X0)") (class "Default")
      (node (ref "IC3") (pin "9") (pinfunction "X0_9") (pintype "input"))
      (node (ref "P0_9") (pin "2") (pinfunction "S_2") (pintype "passive"))
    )
    (net (code "48") (name "Net-(IC3A-X1)") (class "Default")
      (node (ref "IC3") (pin "8") (pinfunction "X1_8") (pintype "input"))
      (node (ref "P0_8") (pin "2") (pinfunction "S_2") (pintype "passive"))
    )
    (net (code "49") (name "Net-(IC3A-X2)") (class "Default")
      (node (ref "IC3") (pin "7") (pinfunction "X2_7") (pintype "input"))
      (node (ref "P0_7") (pin "2") (pinfunction "S_2") (pintype "passive"))
    )
    (net (code "50") (name "Net-(IC3A-X3)") (class "Default")
      (node (ref "IC3") (pin "6") (pinfunction "X3_6") (pintype "input"))
      (node (ref "P0_6") (pin "2") (pinfunction "S_2") (pintype "passive"))
    )
    (net (code "51") (name "Net-(IC3A-X4)") (class "Default")
      (node (ref "IC3") (pin "5") (pinfunction "X4_5") (pintype "input"))
      (node (ref "P0_5") (pin "2") (pinfunction "S_2") (pintype "passive"))
    )
    (net (code "52") (name "Net-(IC3A-X5)") (class "Default")
      (node (ref "IC3") (pin "4") (pinfunction "X5_4") (pintype "input"))
      (node (ref "P0_4") (pin "2") (pinfunction "S_2") (pintype "passive"))
    )
    (net (code "53") (name "Net-(IC3A-X6)") (class "Default")
      (node (ref "IC3") (pin "3") (pinfunction "X6_3") (pintype "input"))
      (node (ref "P0_3") (pin "2") (pinfunction "S_2") (pintype "passive"))
    )
    (net (code "54") (name "Net-(IC3A-X7)") (class "Default")
      (node (ref "IC3") (pin "2") (pinfunction "X7_2") (pintype "input"))
      (node (ref "P0_2") (pin "2") (pinfunction "S_2") (pintype "passive"))
    )
    (net (code "55") (name "Net-(IC3A-X8)") (class "Default")
      (node (ref "IC3") (pin "23") (pinfunction "X8_23") (pintype "input"))
      (node (ref "P0_1") (pin "2") (pinfunction "S_2") (pintype "passive"))
    )
    (net (code "56") (name "Net-(IC3A-X9)") (class "Default")
      (node (ref "IC3") (pin "22") (pinfunction "X9_22") (pintype "input"))
      (node (ref "P0_0") (pin "2") (pinfunction "S_2") (pintype "passive"))
    )
    (net (code "57") (name "Net-(IC4A-X0)") (class "Default")
      (node (ref "IC4") (pin "9") (pinfunction "X0_9") (pintype "input"))
      (node (ref "P1_9") (pin "2") (pinfunction "S_2") (pintype "passive"))
    )
    (net (code "58") (name "Net-(IC4A-X1)") (class "Default")
      (node (ref "IC4") (pin "8") (pinfunction "X1_8") (pintype "input"))
      (node (ref "P1_8") (pin "2") (pinfunction "S_2") (pintype "passive"))
    )
    (net (code "59") (name "Net-(IC4A-X2)") (class "Default")
      (node (ref "IC4") (pin "7") (pinfunction "X2_7") (pintype "input"))
      (node (ref "P1_7") (pin "2") (pinfunction "S_2") (pintype "passive"))
    )
    (net (code "60") (name "Net-(IC4A-X3)") (class "Default")
      (node (ref "IC4") (pin "6") (pinfunction "X3_6") (pintype "input"))
      (node (ref "P1_6") (pin "2") (pinfunction "S_2") (pintype "passive"))
    )
    (net (code "61") (name "Net-(IC4A-X4)") (class "Default")
      (node (ref "IC4") (pin "5") (pinfunction "X4_5") (pintype "input"))
      (node (ref "P1_5") (pin "2") (pinfunction "S_2") (pintype "passive"))
    )
    (net (code "62") (name "Net-(IC4A-X5)") (class "Default")
      (node (ref "IC4") (pin "4") (pinfunction "X5_4") (pintype "input"))
      (node (ref "P1_4") (pin "2") (pinfunction "S_2") (pintype "passive"))
    )
    (net (code "63") (name "Net-(IC4A-X6)") (class "Default")
      (node (ref "IC4") (pin "3") (pinfunction "X6_3") (pintype "input"))
      (node (ref "P1_3") (pin "2") (pinfunction "S_2") (pintype "passive"))
    )
    (net (code "64") (name "Net-(IC4A-X7)") (class "Default")
      (node (ref "IC4") (pin "2") (pinfunction "X7_2") (pintype "input"))
      (node (ref "P1_2") (pin "2") (pinfunction "S_2") (pintype "passive"))
    )
    (net (code "65") (name "Net-(IC4A-X8)") (class "Default")
      (node (ref "IC4") (pin "23") (pinfunction "X8_23") (pintype "input"))
      (node (ref "P1_1") (pin "2") (pinfunction "S_2") (pintype "passive"))
    )
    (net (code "66") (name "Net-(IC4A-X9)") (class "Default")
      (node (ref "IC4") (pin "22") (pinfunction "X9_22") (pintype "input"))
      (node (ref "P1_0") (pin "2") (pinfunction "S_2") (pintype "passive"))
    )
    (net (code "67") (name "Net-(IC5A-X0)") (class "Default")
      (node (ref "IC5") (pin "9") (pinfunction "X0_9") (pintype "input"))
      (node (ref "MS9") (pin "4") (pinfunction "P1_4") (pintype "passive"))
    )
    (net (code "68") (name "Net-(IC5A-X1)") (class "Default")
      (node (ref "IC5") (pin "8") (pinfunction "X1_8") (pintype "input"))
      (node (ref "MS8") (pin "4") (pinfunction "P1_4") (pintype "passive"))
    )
    (net (code "69") (name "Net-(IC5A-X2)") (class "Default")
      (node (ref "IC5") (pin "7") (pinfunction "X2_7") (pintype "input"))
      (node (ref "MS7") (pin "4") (pinfunction "P1_4") (pintype "passive"))
    )
    (net (code "70") (name "Net-(IC5A-X3)") (class "Default")
      (node (ref "IC5") (pin "6") (pinfunction "X3_6") (pintype "input"))
      (node (ref "MS6") (pin "4") (pinfunction "P1_4") (pintype "passive"))
    )
    (net (code "71") (name "Net-(IC5A-X4)") (class "Default")
      (node (ref "IC5") (pin "5") (pinfunction "X4_5") (pintype "input"))
      (node (ref "MS5") (pin "4") (pinfunction "P1_4") (pintype "passive"))
    )
    (net (code "72") (name "Net-(IC5A-X5)") (class "Default")
      (node (ref "IC5") (pin "4") (pinfunction "X5_4") (pintype "input"))
      (node (ref "MS4") (pin "4") (pinfunction "P1_4") (pintype "passive"))
    )
    (net (code "73") (name "Net-(IC5A-X6)") (class "Default")
      (node (ref "IC5") (pin "3") (pinfunction "X6_3") (pintype "input"))
      (node (ref "MS3") (pin "4") (pinfunction "P1_4") (pintype "passive"))
    )
    (net (code "74") (name "Net-(IC5A-X7)") (class "Default")
      (node (ref "IC5") (pin "2") (pinfunction "X7_2") (pintype "input"))
      (node (ref "MS2") (pin "4") (pinfunction "P1_4") (pintype "passive"))
    )
    (net (code "75") (name "Net-(IC5A-X8)") (class "Default")
      (node (ref "IC5") (pin "23") (pinfunction "X8_23") (pintype "input"))
      (node (ref "MS1") (pin "4") (pinfunction "P1_4") (pintype "passive"))
    )
    (net (code "76") (name "Net-(IC5A-X9)") (class "Default")
      (node (ref "IC5") (pin "22") (pinfunction "X9_22") (pintype "input"))
      (node (ref "MS0") (pin "4") (pinfunction "P1_4") (pintype "passive"))
    )
    (net (code "77") (name "Net-(LED0-PadA)") (class "Default")
      (node (ref "LED0") (pin "A") (pinfunction "A_A") (pintype "passive"))
      (node (ref "R40") (pin "1") (pinfunction "1_1") (pintype "passive"))
    )
    (net (code "78") (name "Net-(LED1-PadA)") (class "Default")
      (node (ref "LED1") (pin "A") (pinfunction "A_A") (pintype "passive"))
      (node (ref "R39") (pin "1") (pinfunction "1_1") (pintype "passive"))
    )
    (net (code "79") (name "Net-(LED2-PadA)") (class "Default")
      (node (ref "LED2") (pin "A") (pinfunction "A_A") (pintype "passive"))
      (node (ref "R41") (pin "1") (pinfunction "1_1") (pintype "passive"))
    )
    (net (code "80") (name "Net-(LED3-PadA)") (class "Default")
      (node (ref "LED3") (pin "A") (pinfunction "A_A") (pintype "passive"))
      (node (ref "R42") (pin "1") (pinfunction "1_1") (pintype "passive"))
    )
    (net (code "81") (name "Net-(LED4-PadA)") (class "Default")
      (node (ref "LED4") (pin "A") (pinfunction "A_A") (pintype "passive"))
      (node (ref "R43") (pin "1") (pinfunction "1_1") (pintype "passive"))
    )
    (net (code "82") (name "Net-(LED5-PadA)") (class "Default")
      (node (ref "LED5") (pin "A") (pinfunction "A_A") (pintype "passive"))
      (node (ref "R44") (pin "1") (pinfunction "1_1") (pintype "passive"))
    )
    (net (code "83") (name "Net-(LED6-PadA)") (class "Default")
      (node (ref "LED6") (pin "A") (pinfunction "A_A") (pintype "passive"))
      (node (ref "R45") (pin "1") (pinfunction "1_1") (pintype "passive"))
    )
    (net (code "84") (name "Net-(LED7-PadA)") (class "Default")
      (node (ref "LED7") (pin "A") (pinfunction "A_A") (pintype "passive"))
      (node (ref "R46") (pin "1") (pinfunction "1_1") (pintype "passive"))
    )
    (net (code "85") (name "Net-(LED8-PadA)") (class "Default")
      (node (ref "LED8") (pin "A") (pinfunction "A_A") (pintype "passive"))
      (node (ref "R47") (pin "1") (pinfunction "1_1") (pintype "passive"))
    )
    (net (code "86") (name "Net-(LED9-PadA)") (class "Default")
      (node (ref "LED9") (pin "A") (pinfunction "A_A") (pintype "passive"))
      (node (ref "R48") (pin "1") (pinfunction "1_1") (pintype "passive"))
    )
    (net (code "87") (name "Net-(MS0-P)") (class "Default")
      (node (ref "MS0") (pin "3") (pinfunction "P_3") (pintype "passive"))
      (node (ref "R29") (pin "2") (pinfunction "2_2") (pintype "passive"))
    )
    (net (code "88") (name "Net-(MS1-P)") (class "Default")
      (node (ref "MS1") (pin "3") (pinfunction "P_3") (pintype "passive"))
      (node (ref "R30") (pin "2") (pinfunction "2_2") (pintype "passive"))
    )
    (net (code "89") (name "Net-(MS2-P)") (class "Default")
      (node (ref "MS2") (pin "3") (pinfunction "P_3") (pintype "passive"))
      (node (ref "R31") (pin "2") (pinfunction "2_2") (pintype "passive"))
    )
    (net (code "90") (name "Net-(MS3-P)") (class "Default")
      (node (ref "MS3") (pin "3") (pinfunction "P_3") (pintype "passive"))
      (node (ref "R32") (pin "2") (pinfunction "2_2") (pintype "passive"))
    )
    (net (code "91") (name "Net-(MS4-P)") (class "Default")
      (node (ref "MS4") (pin "3") (pinfunction "P_3") (pintype "passive"))
      (node (ref "R38") (pin "2") (pinfunction "2_2") (pintype "passive"))
    )
    (net (code "92") (name "Net-(MS5-P)") (class "Default")
      (node (ref "MS5") (pin "3") (pinfunction "P_3") (pintype "passive"))
      (node (ref "R33") (pin "2") (pinfunction "2_2") (pintype "passive"))
    )
    (net (code "93") (name "Net-(MS6-P)") (class "Default")
      (node (ref "MS6") (pin "3") (pinfunction "P_3") (pintype "passive"))
      (node (ref "R34") (pin "2") (pinfunction "2_2") (pintype "passive"))
    )
    (net (code "94") (name "Net-(MS7-P)") (class "Default")
      (node (ref "MS7") (pin "3") (pinfunction "P_3") (pintype "passive"))
      (node (ref "R35") (pin "2") (pinfunction "2_2") (pintype "passive"))
    )
    (net (code "95") (name "Net-(MS8-P)") (class "Default")
      (node (ref "MS8") (pin "3") (pinfunction "P_3") (pintype "passive"))
      (node (ref "R36") (pin "2") (pinfunction "2_2") (pintype "passive"))
    )
    (net (code "96") (name "Net-(MS9-P)") (class "Default")
      (node (ref "MS9") (pin "3") (pinfunction "P_3") (pintype "passive"))
      (node (ref "R37") (pin "2") (pinfunction "2_2") (pintype "passive"))
    )
    (net (code "97") (name "Net-(SW0-P)") (class "Default")
      (node (ref "R1") (pin "2") (pinfunction "2_2") (pintype "passive"))
      (node (ref "SW0") (pin "3") (pinfunction "P_3") (pintype "passive"))
    )
    (net (code "98") (name "Net-(SW1-P)") (class "Default")
      (node (ref "R2") (pin "2") (pinfunction "2_2") (pintype "passive"))
      (node (ref "SW1") (pin "3") (pinfunction "P_3") (pintype "passive"))
    )
    (net (code "99") (name "Net-(SW2-P)") (class "Default")
      (node (ref "R3") (pin "2") (pinfunction "2_2") (pintype "passive"))
      (node (ref "SW2") (pin "3") (pinfunction "P_3") (pintype "passive"))
    )
    (net (code "100") (name "Net-(SW3-P)") (class "Default")
      (node (ref "R4") (pin "2") (pinfunction "2_2") (pintype "passive"))
      (node (ref "SW3") (pin "3") (pinfunction "P_3") (pintype "passive"))
    )
    (net (code "101") (name "Net-(SW4-P)") (class "Default")
      (node (ref "R10") (pin "2") (pinfunction "2_2") (pintype "passive"))
      (node (ref "SW4") (pin "3") (pinfunction "P_3") (pintype "passive"))
    )
    (net (code "102") (name "Net-(SW5-P)") (class "Default")
      (node (ref "R5") (pin "2") (pinfunction "2_2") (pintype "passive"))
      (node (ref "SW5") (pin "3") (pinfunction "P_3") (pintype "passive"))
    )
    (net (code "103") (name "Net-(SW6-P)") (class "Default")
      (node (ref "R6") (pin "2") (pinfunction "2_2") (pintype "passive"))
      (node (ref "SW6") (pin "3") (pinfunction "P_3") (pintype "passive"))
    )
    (net (code "104") (name "Net-(SW7-P)") (class "Default")
      (node (ref "R7") (pin "2") (pinfunction "2_2") (pintype "passive"))
      (node (ref "SW7") (pin "3") (pinfunction "P_3") (pintype "passive"))
    )
    (net (code "105") (name "Net-(SW8-P)") (class "Default")
      (node (ref "R8") (pin "2") (pinfunction "2_2") (pintype "passive"))
      (node (ref "SW8") (pin "3") (pinfunction "P_3") (pintype "passive"))
    )
    (net (code "106") (name "Net-(SW9-P)") (class "Default")
      (node (ref "R9") (pin "2") (pinfunction "2_2") (pintype "passive"))
      (node (ref "SW9") (pin "3") (pinfunction "P_3") (pintype "passive"))
    )
    (net (code "107") (name "Net-(T1-B)") (class "Default")
      (node (ref "R11") (pin "2") (pinfunction "2_2") (pintype "passive"))
      (node (ref "T1") (pin "2") (pinfunction "B_2") (pintype "passive"))
    )
    (net (code "108") (name "Net-(T2-B)") (class "Default")
      (node (ref "R12") (pin "2") (pinfunction "2_2") (pintype "passive"))
      (node (ref "T2") (pin "2") (pinfunction "B_2") (pintype "passive"))
    )
    (net (code "109") (name "Net-(T3-B)") (class "Default")
      (node (ref "R13") (pin "2") (pinfunction "2_2") (pintype "passive"))
      (node (ref "T3") (pin "2") (pinfunction "B_2") (pintype "passive"))
    )
    (net (code "110") (name "Net-(T4-B)") (class "Default")
      (node (ref "R14") (pin "2") (pinfunction "2_2") (pintype "passive"))
      (node (ref "T4") (pin "2") (pinfunction "B_2") (pintype "passive"))
    )
    (net (code "111") (name "Net-(T5-B)") (class "Default")
      (node (ref "R15") (pin "2") (pinfunction "2_2") (pintype "passive"))
      (node (ref "T5") (pin "2") (pinfunction "B_2") (pintype "passive"))
    )
    (net (code "112") (name "Net-(T6-B)") (class "Default")
      (node (ref "R24") (pin "2") (pinfunction "2_2") (pintype "passive"))
      (node (ref "T6") (pin "2") (pinfunction "B_2") (pintype "passive"))
    )
    (net (code "113") (name "Net-(T7-B)") (class "Default")
      (node (ref "R25") (pin "2") (pinfunction "2_2") (pintype "passive"))
      (node (ref "T7") (pin "2") (pinfunction "B_2") (pintype "passive"))
    )
    (net (code "114") (name "Net-(T8-B)") (class "Default")
      (node (ref "R26") (pin "2") (pinfunction "2_2") (pintype "passive"))
      (node (ref "T8") (pin "2") (pinfunction "B_2") (pintype "passive"))
    )
    (net (code "115") (name "Net-(T9-B)") (class "Default")
      (node (ref "R27") (pin "2") (pinfunction "2_2") (pintype "passive"))
      (node (ref "T9") (pin "2") (pinfunction "B_2") (pintype "passive"))
    )
    (net (code "116") (name "Net-(T10-B)") (class "Default")
      (node (ref "R28") (pin "2") (pinfunction "2_2") (pintype "passive"))
      (node (ref "T10") (pin "2") (pinfunction "B_2") (pintype "passive"))
    )
    (net (code "117") (name "POT0_INH") (class "Default")
      (node (ref "IC3") (pin "15") (pinfunction "INH_15") (pintype "input"))
      (node (ref "U$1") (pin "8-TX2/IN1") (pinfunction "8-TX2/IN1_8-TX2/IN1") (pintype "bidirectional"))
    )
    (net (code "118") (name "POT0_X") (class "Default")
      (node (ref "IC3") (pin "1") (pinfunction "X_1") (pintype "output"))
      (node (ref "U$1") (pin "16-A2/RX4/SCL1") (pinfunction "16-A2/RX4/SCL1_16-A2/RX4/SCL1") (pintype "bidirectional"))
    )
    (net (code "119") (name "POT1_INH") (class "Default")
      (node (ref "IC4") (pin "15") (pinfunction "INH_15") (pintype "input"))
      (node (ref "U$1") (pin "9-OUT1C") (pinfunction "9-OUT1C_9-OUT1C") (pintype "bidirectional"))
    )
    (net (code "120") (name "POT1_X") (class "Default")
      (node (ref "IC4") (pin "1") (pinfunction "X_1") (pintype "output"))
      (node (ref "U$1") (pin "17-A3/TX4/SDA1") (pinfunction "17-A3/TX4/SDA1_17-A3/TX4/SDA1") (pintype "bidirectional"))
    )
    (net (code "121") (name "POT2_X") (class "Default")
      (node (ref "U$1") (pin "18-A4/SDA0") (pinfunction "18-A4/SDA0_18-A4/SDA0") (pintype "bidirectional"))
    )
    (net (code "122") (name "SEG_A") (class "Default")
      (node (ref "R16") (pin "1") (pinfunction "1_1") (pintype "passive"))
      (node (ref "U$1") (pin "39-A15/CS/OUT1A") (pinfunction "39-A15/CS/OUT1A_39-A15/CS/OUT1A") (pintype "bidirectional"))
    )
    (net (code "123") (name "SEG_B") (class "Default")
      (node (ref "R17") (pin "1") (pinfunction "1_1") (pintype "passive"))
      (node (ref "U$1") (pin "40-A16/CS1") (pinfunction "40-A16/CS1_40-A16/CS1") (pintype "bidirectional"))
    )
    (net (code "124") (name "SEG_C") (class "Default")
      (node (ref "R18") (pin "1") (pinfunction "1_1") (pintype "passive"))
      (node (ref "U$1") (pin "41-A17/MISO1") (pinfunction "41-A17/MISO1_41-A17/MISO1") (pintype "bidirectional"))
    )
    (net (code "125") (name "SEG_D") (class "Default")
      (node (ref "R19") (pin "1") (pinfunction "1_1") (pintype "passive"))
      (node (ref "U$1") (pin "30-CRX3") (pinfunction "30-CRX3_30-CRX3") (pintype "bidirectional"))
    )
    (net (code "126") (name "SEG_E") (class "Default")
      (node (ref "R20") (pin "1") (pinfunction "1_1") (pintype "passive"))
      (node (ref "U$1") (pin "31-CTX3") (pinfunction "31-CTX3_31-CTX3") (pintype "bidirectional"))
    )
    (net (code "127") (name "SEG_F") (class "Default")
      (node (ref "R21") (pin "1") (pinfunction "1_1") (pintype "passive"))
      (node (ref "U$1") (pin "28-RX7") (pinfunction "28-RX7_28-RX7") (pintype "bidirectional"))
    )
    (net (code "128") (name "SEG_G") (class "Default")
      (node (ref "R22") (pin "1") (pinfunction "1_1") (pintype "passive"))
      (node (ref "U$1") (pin "29-TX7") (pinfunction "29-TX7_29-TX7") (pintype "bidirectional"))
    )
    (net (code "129") (name "SEG_K0") (class "Default")
      (node (ref "R11") (pin "1") (pinfunction "1_1") (pintype "passive"))
      (node (ref "U$1") (pin "19-A5/SCL0") (pinfunction "19-A5/SCL0_19-A5/SCL0") (pintype "bidirectional"))
    )
    (net (code "130") (name "SEG_K1") (class "Default")
      (node (ref "R12") (pin "1") (pinfunction "1_1") (pintype "passive"))
      (node (ref "U$1") (pin "20-A6/TX5/LRCLK1") (pinfunction "20-A6/TX5/LRCLK1_20-A6/TX5/LRCLK1") (pintype "bidirectional"))
    )
    (net (code "131") (name "SEG_K1AA") (class "Default")
      (node (ref "D1") (pin "3") (pinfunction "CK1_3") (pintype "passive"))
      (node (ref "D1") (pin "8") (pinfunction "CK2_8") (pintype "passive"))
      (node (ref "T2") (pin "3") (pinfunction "C_3") (pintype "passive"))
    )
    (net (code "132") (name "SEG_K1AAAAV") (class "Default")
      (node (ref "D6") (pin "3") (pinfunction "CK1_3") (pintype "passive"))
      (node (ref "D6") (pin "8") (pinfunction "CK2_8") (pintype "passive"))
      (node (ref "T7") (pin "3") (pinfunction "C_3") (pintype "passive"))
    )
    (net (code "133") (name "SEG_K2") (class "Default")
      (node (ref "R13") (pin "1") (pinfunction "1_1") (pintype "passive"))
      (node (ref "U$1") (pin "21-A7/RX5/BCLK1") (pinfunction "21-A7/RX5/BCLK1_21-A7/RX5/BCLK1") (pintype "bidirectional"))
    )
    (net (code "134") (name "SEG_K2AA") (class "Default")
      (node (ref "D2") (pin "3") (pinfunction "CK1_3") (pintype "passive"))
      (node (ref "D2") (pin "8") (pinfunction "CK2_8") (pintype "passive"))
      (node (ref "T3") (pin "3") (pinfunction "C_3") (pintype "passive"))
    )
    (net (code "135") (name "SEG_K2VVV") (class "Default")
      (node (ref "D7") (pin "3") (pinfunction "CK1_3") (pintype "passive"))
      (node (ref "D7") (pin "8") (pinfunction "CK2_8") (pintype "passive"))
      (node (ref "T8") (pin "3") (pinfunction "C_3") (pintype "passive"))
    )
    (net (code "136") (name "SEG_K3") (class "Default")
      (node (ref "R14") (pin "1") (pinfunction "1_1") (pintype "passive"))
      (node (ref "U$1") (pin "22-A8/CTX1") (pinfunction "22-A8/CTX1_22-A8/CTX1") (pintype "bidirectional"))
    )
    (net (code "137") (name "SEG_K3AA") (class "Default")
      (node (ref "D3") (pin "3") (pinfunction "CK1_3") (pintype "passive"))
      (node (ref "D3") (pin "8") (pinfunction "CK2_8") (pintype "passive"))
      (node (ref "T4") (pin "3") (pinfunction "C_3") (pintype "passive"))
    )
    (net (code "138") (name "SEG_K3VVV") (class "Default")
      (node (ref "D8") (pin "3") (pinfunction "CK1_3") (pintype "passive"))
      (node (ref "D8") (pin "8") (pinfunction "CK2_8") (pintype "passive"))
      (node (ref "T9") (pin "3") (pinfunction "C_3") (pintype "passive"))
    )
    (net (code "139") (name "SEG_K4") (class "Default")
      (node (ref "R15") (pin "1") (pinfunction "1_1") (pintype "passive"))
      (node (ref "U$1") (pin "23-A9/CRX1/MCLK1") (pinfunction "23-A9/CRX1/MCLK1_23-A9/CRX1/MCLK1") (pintype "bidirectional"))
    )
    (net (code "140") (name "SEG_K4AA") (class "Default")
      (node (ref "D4") (pin "3") (pinfunction "CK1_3") (pintype "passive"))
      (node (ref "D4") (pin "8") (pinfunction "CK2_8") (pintype "passive"))
      (node (ref "T5") (pin "3") (pinfunction "C_3") (pintype "passive"))
    )
    (net (code "141") (name "SEG_K4VDF") (class "Default")
      (node (ref "D9") (pin "3") (pinfunction "CK1_3") (pintype "passive"))
      (node (ref "D9") (pin "8") (pinfunction "CK2_8") (pintype "passive"))
      (node (ref "T10") (pin "3") (pinfunction "C_3") (pintype "passive"))
    )
    (net (code "142") (name "SEG_K5") (class "Default")
      (node (ref "R24") (pin "1") (pinfunction "1_1") (pintype "passive"))
      (node (ref "U$1") (pin "24-A10/TX6/SCL2") (pinfunction "24-A10/TX6/SCL2_24-A10/TX6/SCL2") (pintype "bidirectional"))
    )
    (net (code "143") (name "SEG_K6") (class "Default")
      (node (ref "R25") (pin "1") (pinfunction "1_1") (pintype "passive"))
      (node (ref "U$1") (pin "25-A11/RX6/SDA2") (pinfunction "25-A11/RX6/SDA2_25-A11/RX6/SDA2") (pintype "bidirectional"))
    )
    (net (code "144") (name "SEG_K7") (class "Default")
      (node (ref "R26") (pin "1") (pinfunction "1_1") (pintype "passive"))
      (node (ref "U$1") (pin "26-A12/MOSI1") (pinfunction "26-A12/MOSI1_26-A12/MOSI1") (pintype "bidirectional"))
    )
    (net (code "145") (name "SEG_K8") (class "Default")
      (node (ref "R27") (pin "1") (pinfunction "1_1") (pintype "passive"))
      (node (ref "U$1") (pin "27-A13/SCK1") (pinfunction "27-A13/SCK1_27-A13/SCK1") (pintype "bidirectional"))
    )
    (net (code "146") (name "SEG_K9") (class "Default")
      (node (ref "R28") (pin "1") (pinfunction "1_1") (pintype "passive"))
      (node (ref "U$1") (pin "38-A14/CS/IN1") (pinfunction "38-A14/CS/IN1_38-A14/CS/IN1") (pintype "bidirectional"))
    )
    (net (code "147") (name "SEG_P") (class "Default")
      (node (ref "R23") (pin "1") (pinfunction "1_1") (pintype "passive"))
      (node (ref "U$1") (pin "34-RX8") (pinfunction "34-RX8_34-RX8") (pintype "bidirectional"))
    )
    (net (code "148") (name "SIG_K0AA") (class "Default")
      (node (ref "D0") (pin "3") (pinfunction "CK1_3") (pintype "passive"))
      (node (ref "D0") (pin "8") (pinfunction "CK2_8") (pintype "passive"))
      (node (ref "T1") (pin "3") (pinfunction "C_3") (pintype "passive"))
    )
    (net (code "149") (name "SIG_K1AA") (class "Default")
      (node (ref "D5") (pin "3") (pinfunction "CK1_3") (pintype "passive"))
      (node (ref "D5") (pin "8") (pinfunction "CK2_8") (pintype "passive"))
      (node (ref "T6") (pin "3") (pinfunction "C_3") (pintype "passive"))
    )
    (net (code "150") (name "SWITCH2_INH") (class "Default")
      (node (ref "IC5") (pin "15") (pinfunction "INH_15") (pintype "input"))
      (node (ref "U$1") (pin "10-CS\\MQSR") (pinfunction "10-CS/MQSR_10-CS\\MQSR") (pintype "bidirectional"))
    )
    (net (code "151") (name "SWITCH2_X") (class "Default")
      (node (ref "IC5") (pin "1") (pinfunction "X_1") (pintype "output"))
    )
    (net (code "152") (name "SWITCH_INH") (class "Default")
      (node (ref "IC2") (pin "15") (pinfunction "INH_15") (pintype "input"))
      (node (ref "U$1") (pin "7-RX2/OUT1A") (pinfunction "7-RX2/OUT1A_7-RX2/OUT1A") (pintype "bidirectional"))
    )
    (net (code "153") (name "SWITCH_X") (class "Default")
      (node (ref "IC2") (pin "1") (pinfunction "X_1") (pintype "output"))
      (node (ref "U$1") (pin "15-A1/RX3/SPDIF_IN") (pinfunction "15-A1/RX3/SPDIF_IN_15-A1/RX3/SPDIF_IN") (pintype "bidirectional"))
    )
    (net (code "154") (name "unconnected-(IC1A-X10-Pad21)") (class "Default")
      (node (ref "IC1") (pin "21") (pinfunction "X10_21") (pintype "input"))
    )
    (net (code "155") (name "unconnected-(IC1A-X11-Pad20)") (class "Default")
      (node (ref "IC1") (pin "20") (pinfunction "X11_20") (pintype "input"))
    )
    (net (code "156") (name "unconnected-(IC1A-X12-Pad19)") (class "Default")
      (node (ref "IC1") (pin "19") (pinfunction "X12_19") (pintype "input"))
    )
    (net (code "157") (name "unconnected-(IC1A-X13-Pad18)") (class "Default")
      (node (ref "IC1") (pin "18") (pinfunction "X13_18") (pintype "input"))
    )
    (net (code "158") (name "unconnected-(IC1A-X14-Pad17)") (class "Default")
      (node (ref "IC1") (pin "17") (pinfunction "X14_17") (pintype "input"))
    )
    (net (code "159") (name "unconnected-(IC1A-X15-Pad16)") (class "Default")
      (node (ref "IC1") (pin "16") (pinfunction "X15_16") (pintype "input"))
    )
    (net (code "160") (name "unconnected-(IC2A-X10-Pad21)") (class "Default")
      (node (ref "IC2") (pin "21") (pinfunction "X10_21") (pintype "input"))
    )
    (net (code "161") (name "unconnected-(IC2A-X11-Pad20)") (class "Default")
      (node (ref "IC2") (pin "20") (pinfunction "X11_20") (pintype "input"))
    )
    (net (code "162") (name "unconnected-(IC2A-X12-Pad19)") (class "Default")
      (node (ref "IC2") (pin "19") (pinfunction "X12_19") (pintype "input"))
    )
    (net (code "163") (name "unconnected-(IC2A-X13-Pad18)") (class "Default")
      (node (ref "IC2") (pin "18") (pinfunction "X13_18") (pintype "input"))
    )
    (net (code "164") (name "unconnected-(IC2A-X14-Pad17)") (class "Default")
      (node (ref "IC2") (pin "17") (pinfunction "X14_17") (pintype "input"))
    )
    (net (code "165") (name "unconnected-(IC2A-X15-Pad16)") (class "Default")
      (node (ref "IC2") (pin "16") (pinfunction "X15_16") (pintype "input"))
    )
    (net (code "166") (name "unconnected-(IC3A-X10-Pad21)") (class "Default")
      (node (ref "IC3") (pin "21") (pinfunction "X10_21") (pintype "input"))
    )
    (net (code "167") (name "unconnected-(IC3A-X11-Pad20)") (class "Default")
      (node (ref "IC3") (pin "20") (pinfunction "X11_20") (pintype "input"))
    )
    (net (code "168") (name "unconnected-(IC3A-X12-Pad19)") (class "Default")
      (node (ref "IC3") (pin "19") (pinfunction "X12_19") (pintype "input"))
    )
    (net (code "169") (name "unconnected-(IC3A-X13-Pad18)") (class "Default")
      (node (ref "IC3") (pin "18") (pinfunction "X13_18") (pintype "input"))
    )
    (net (code "170") (name "unconnected-(IC3A-X14-Pad17)") (class "Default")
      (node (ref "IC3") (pin "17") (pinfunction "X14_17") (pintype "input"))
    )
    (net (code "171") (name "unconnected-(IC3A-X15-Pad16)") (class "Default")
      (node (ref "IC3") (pin "16") (pinfunction "X15_16") (pintype "input"))
    )
    (net (code "172") (name "unconnected-(IC4A-X10-Pad21)") (class "Default")
      (node (ref "IC4") (pin "21") (pinfunction "X10_21") (pintype "input"))
    )
    (net (code "173") (name "unconnected-(IC4A-X11-Pad20)") (class "Default")
      (node (ref "IC4") (pin "20") (pinfunction "X11_20") (pintype "input"))
    )
    (net (code "174") (name "unconnected-(IC4A-X12-Pad19)") (class "Default")
      (node (ref "IC4") (pin "19") (pinfunction "X12_19") (pintype "input"))
    )
    (net (code "175") (name "unconnected-(IC4A-X13-Pad18)") (class "Default")
      (node (ref "IC4") (pin "18") (pinfunction "X13_18") (pintype "input"))
    )
    (net (code "176") (name "unconnected-(IC4A-X14-Pad17)") (class "Default")
      (node (ref "IC4") (pin "17") (pinfunction "X14_17") (pintype "input"))
    )
    (net (code "177") (name "unconnected-(IC4A-X15-Pad16)") (class "Default")
      (node (ref "IC4") (pin "16") (pinfunction "X15_16") (pintype "input"))
    )
    (net (code "178") (name "unconnected-(IC5A-X10-Pad21)") (class "Default")
      (node (ref "IC5") (pin "21") (pinfunction "X10_21") (pintype "input"))
    )
    (net (code "179") (name "unconnected-(IC5A-X11-Pad20)") (class "Default")
      (node (ref "IC5") (pin "20") (pinfunction "X11_20") (pintype "input"))
    )
    (net (code "180") (name "unconnected-(IC5A-X12-Pad19)") (class "Default")
      (node (ref "IC5") (pin "19") (pinfunction "X12_19") (pintype "input"))
    )
    (net (code "181") (name "unconnected-(IC5A-X13-Pad18)") (class "Default")
      (node (ref "IC5") (pin "18") (pinfunction "X13_18") (pintype "input"))
    )
    (net (code "182") (name "unconnected-(IC5A-X14-Pad17)") (class "Default")
      (node (ref "IC5") (pin "17") (pinfunction "X14_17") (pintype "input"))
    )
    (net (code "183") (name "unconnected-(IC5A-X15-Pad16)") (class "Default")
      (node (ref "IC5") (pin "16") (pinfunction "X15_16") (pintype "input"))
    )
    (net (code "184") (name "unconnected-(MS0-S1-Pad2)") (class "Default")
      (node (ref "MS0") (pin "2") (pinfunction "S1_2") (pintype "passive"))
    )
    (net (code "185") (name "unconnected-(MS1-S1-Pad2)") (class "Default")
      (node (ref "MS1") (pin "2") (pinfunction "S1_2") (pintype "passive"))
    )
    (net (code "186") (name "unconnected-(MS2-S1-Pad2)") (class "Default")
      (node (ref "MS2") (pin "2") (pinfunction "S1_2") (pintype "passive"))
    )
    (net (code "187") (name "unconnected-(MS3-S1-Pad2)") (class "Default")
      (node (ref "MS3") (pin "2") (pinfunction "S1_2") (pintype "passive"))
    )
    (net (code "188") (name "unconnected-(MS4-S1-Pad2)") (class "Default")
      (node (ref "MS4") (pin "2") (pinfunction "S1_2") (pintype "passive"))
    )
    (net (code "189") (name "unconnected-(MS5-S1-Pad2)") (class "Default")
      (node (ref "MS5") (pin "2") (pinfunction "S1_2") (pintype "passive"))
    )
    (net (code "190") (name "unconnected-(MS6-S1-Pad2)") (class "Default")
      (node (ref "MS6") (pin "2") (pinfunction "S1_2") (pintype "passive"))
    )
    (net (code "191") (name "unconnected-(MS7-S1-Pad2)") (class "Default")
      (node (ref "MS7") (pin "2") (pinfunction "S1_2") (pintype "passive"))
    )
    (net (code "192") (name "unconnected-(MS8-S1-Pad2)") (class "Default")
      (node (ref "MS8") (pin "2") (pinfunction "S1_2") (pintype "passive"))
    )
    (net (code "193") (name "unconnected-(MS9-S1-Pad2)") (class "Default")
      (node (ref "MS9") (pin "2") (pinfunction "S1_2") (pintype "passive"))
    )
    (net (code "194") (name "unconnected-(SW0-S1-Pad2)") (class "Default")
      (node (ref "SW0") (pin "2") (pinfunction "S1_2") (pintype "passive"))
    )
    (net (code "195") (name "unconnected-(SW1-S1-Pad2)") (class "Default")
      (node (ref "SW1") (pin "2") (pinfunction "S1_2") (pintype "passive"))
    )
    (net (code "196") (name "unconnected-(SW2-S1-Pad2)") (class "Default")
      (node (ref "SW2") (pin "2") (pinfunction "S1_2") (pintype "passive"))
    )
    (net (code "197") (name "unconnected-(SW3-S1-Pad2)") (class "Default")
      (node (ref "SW3") (pin "2") (pinfunction "S1_2") (pintype "passive"))
    )
    (net (code "198") (name "unconnected-(SW4-S1-Pad2)") (class "Default")
      (node (ref "SW4") (pin "2") (pinfunction "S1_2") (pintype "passive"))
    )
    (net (code "199") (name "unconnected-(SW5-S1-Pad2)") (class "Default")
      (node (ref "SW5") (pin "2") (pinfunction "S1_2") (pintype "passive"))
    )
    (net (code "200") (name "unconnected-(SW6-S1-Pad2)") (class "Default")
      (node (ref "SW6") (pin "2") (pinfunction "S1_2") (pintype "passive"))
    )
    (net (code "201") (name "unconnected-(SW7-S1-Pad2)") (class "Default")
      (node (ref "SW7") (pin "2") (pinfunction "S1_2") (pintype "passive"))
    )
    (net (code "202") (name "unconnected-(SW8-S1-Pad2)") (class "Default")
      (node (ref "SW8") (pin "2") (pinfunction "S1_2") (pintype "passive"))
    )
    (net (code "203") (name "unconnected-(SW9-S1-Pad2)") (class "Default")
      (node (ref "SW9") (pin "2") (pinfunction "S1_2") (pintype "passive"))
    )
    (net (code "204") (name "unconnected-(U$1-5V-Pad+5V)") (class "Default")
      (node (ref "U$1") (pin "+5V") (pinfunction "5V_+5V") (pintype "bidirectional"))
    )
    (net (code "205") (name "unconnected-(U$1-Pad3V3-1)") (class "Default")
      (node (ref "U$1") (pin "3V3-1") (pinfunction "3V3-1_3V3-1") (pintype "bidirectional"))
    )
    (net (code "206") (name "unconnected-(U$1-Pad3V3-2)") (class "Default")
      (node (ref "U$1") (pin "3V3-2") (pinfunction "3V3-2_3V3-2") (pintype "bidirectional"))
    )
    (net (code "207") (name "unconnected-(U$1-PadD+)") (class "Default")
      (node (ref "U$1") (pin "D+") (pinfunction "D+_D+") (pintype "bidirectional"))
    )
    (net (code "208") (name "unconnected-(U$1-PadD-)") (class "Default")
      (node (ref "U$1") (pin "D-") (pinfunction "D-_D-") (pintype "bidirectional"))
    )
    (net (code "209") (name "unconnected-(U$1-PadDM)") (class "Default")
      (node (ref "U$1") (pin "DM") (pinfunction "DM_DM") (pintype "bidirectional"))
    )
    (net (code "210") (name "unconnected-(U$1-PadDP)") (class "Default")
      (node (ref "U$1") (pin "DP") (pinfunction "DP_DP") (pintype "bidirectional"))
    )
    (net (code "211") (name "unconnected-(U$1-PadG)") (class "Default")
      (node (ref "U$1") (pin "G") (pinfunction "G_G") (pintype "bidirectional"))
    )
    (net (code "212") (name "unconnected-(U$1-PadGND2)") (class "Default")
      (node (ref "U$1") (pin "GND2") (pinfunction "GND2_GND2") (pintype "bidirectional"))
    )
    (net (code "213") (name "unconnected-(U$1-PadGND3)") (class "Default")
      (node (ref "U$1") (pin "GND3") (pinfunction "GND3_GND3") (pintype "bidirectional"))
    )
    (net (code "214") (name "unconnected-(U$1-PadGND4)") (class "Default")
      (node (ref "U$1") (pin "GND4") (pinfunction "GND4_GND4") (pintype "bidirectional"))
    )
    (net (code "215") (name "unconnected-(U$1-PadGND5)") (class "Default")
      (node (ref "U$1") (pin "GND5") (pinfunction "GND5_GND5") (pintype "bidirectional"))
    )
    (net (code "216") (name "unconnected-(U$1-PadGND6)") (class "Default")
      (node (ref "U$1") (pin "GND6") (pinfunction "GND6_GND6") (pintype "bidirectional"))
    )
    (net (code "217") (name "unconnected-(U$1-PadLED)") (class "Default")
      (node (ref "U$1") (pin "LED") (pinfunction "LED_LED") (pintype "bidirectional"))
    )
    (net (code "218") (name "unconnected-(U$1-PadON{slash}OFF)") (class "Default")
      (node (ref "U$1") (pin "ON/OFF") (pinfunction "ON/OFF_ON/OFF") (pintype "bidirectional"))
    )
    (net (code "219") (name "unconnected-(U$1-PadPROGRAM)") (class "Default")
      (node (ref "U$1") (pin "PROGRAM") (pinfunction "PROGRAM_PROGRAM") (pintype "bidirectional"))
    )
    (net (code "220") (name "unconnected-(U$1-PadR+)") (class "Default")
      (node (ref "U$1") (pin "R+") (pinfunction "R+_R+") (pintype "bidirectional"))
    )
    (net (code "221") (name "unconnected-(U$1-PadR-)") (class "Default")
      (node (ref "U$1") (pin "R-") (pinfunction "R-_R-") (pintype "bidirectional"))
    )
    (net (code "222") (name "unconnected-(U$1-PadT+)") (class "Default")
      (node (ref "U$1") (pin "T+") (pinfunction "T+_T+") (pintype "bidirectional"))
    )
    (net (code "223") (name "unconnected-(U$1-PadT-)") (class "Default")
      (node (ref "U$1") (pin "T-") (pinfunction "T-_T-") (pintype "bidirectional"))
    )
    (net (code "224") (name "unconnected-(U$1-PadVBAT)") (class "Default")
      (node (ref "U$1") (pin "VBAT") (pinfunction "VBAT_VBAT") (pintype "bidirectional"))
    )
    (net (code "225") (name "unconnected-(U$1-PadVIN)") (class "Default")
      (node (ref "U$1") (pin "VIN") (pinfunction "VIN_VIN") (pintype "bidirectional"))
    )
    (net (code "226") (name "unconnected-(U$1-PadVUSB)") (class "Default")
      (node (ref "U$1") (pin "VUSB") (pinfunction "VUSB_VUSB") (pintype "bidirectional"))
    )
  )
)
